# CCM_0011.net
KiCad netlist of a schematic drawn in EAGLE
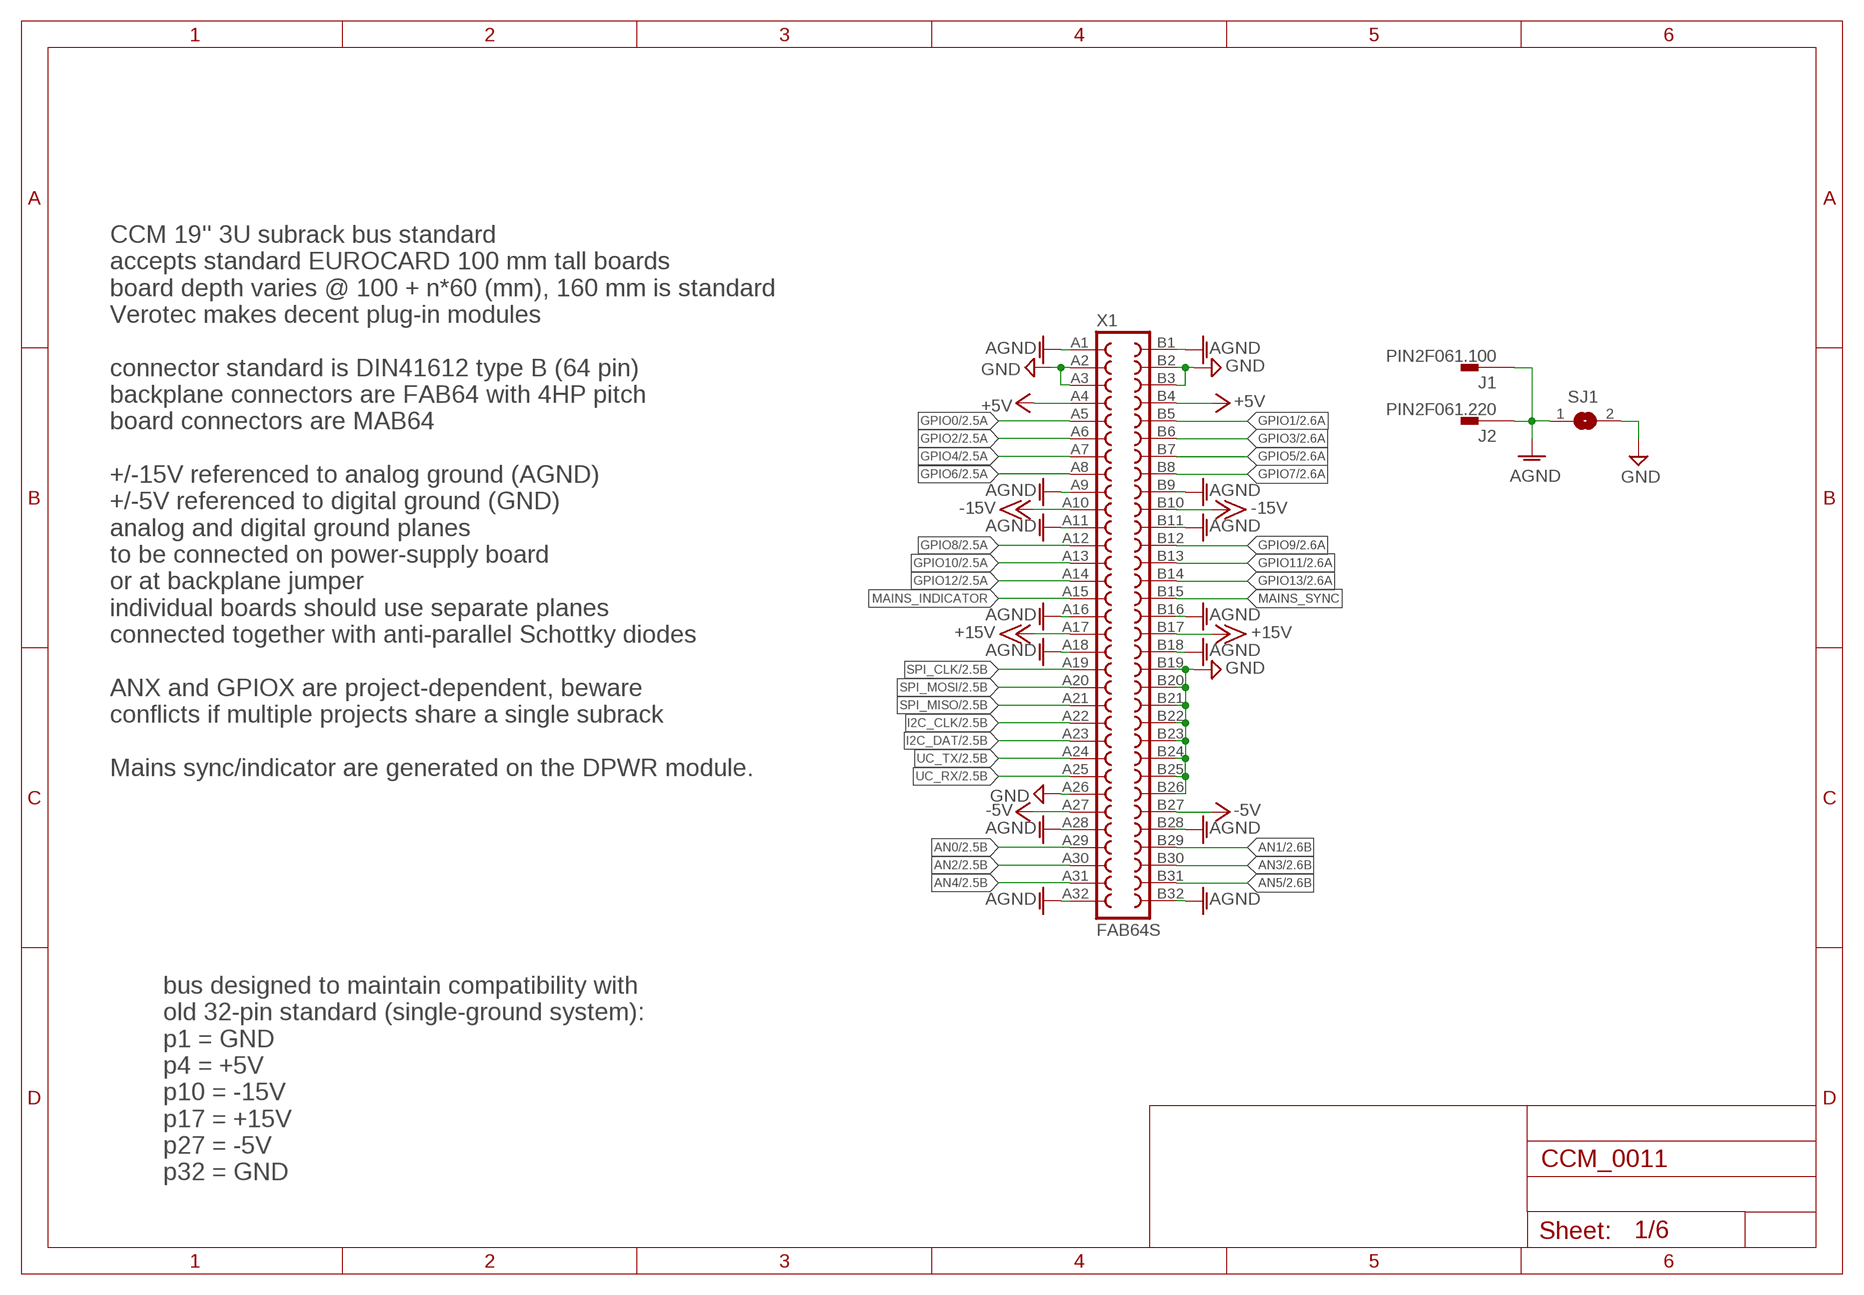
[diagram p0: schematic, sheet 1]
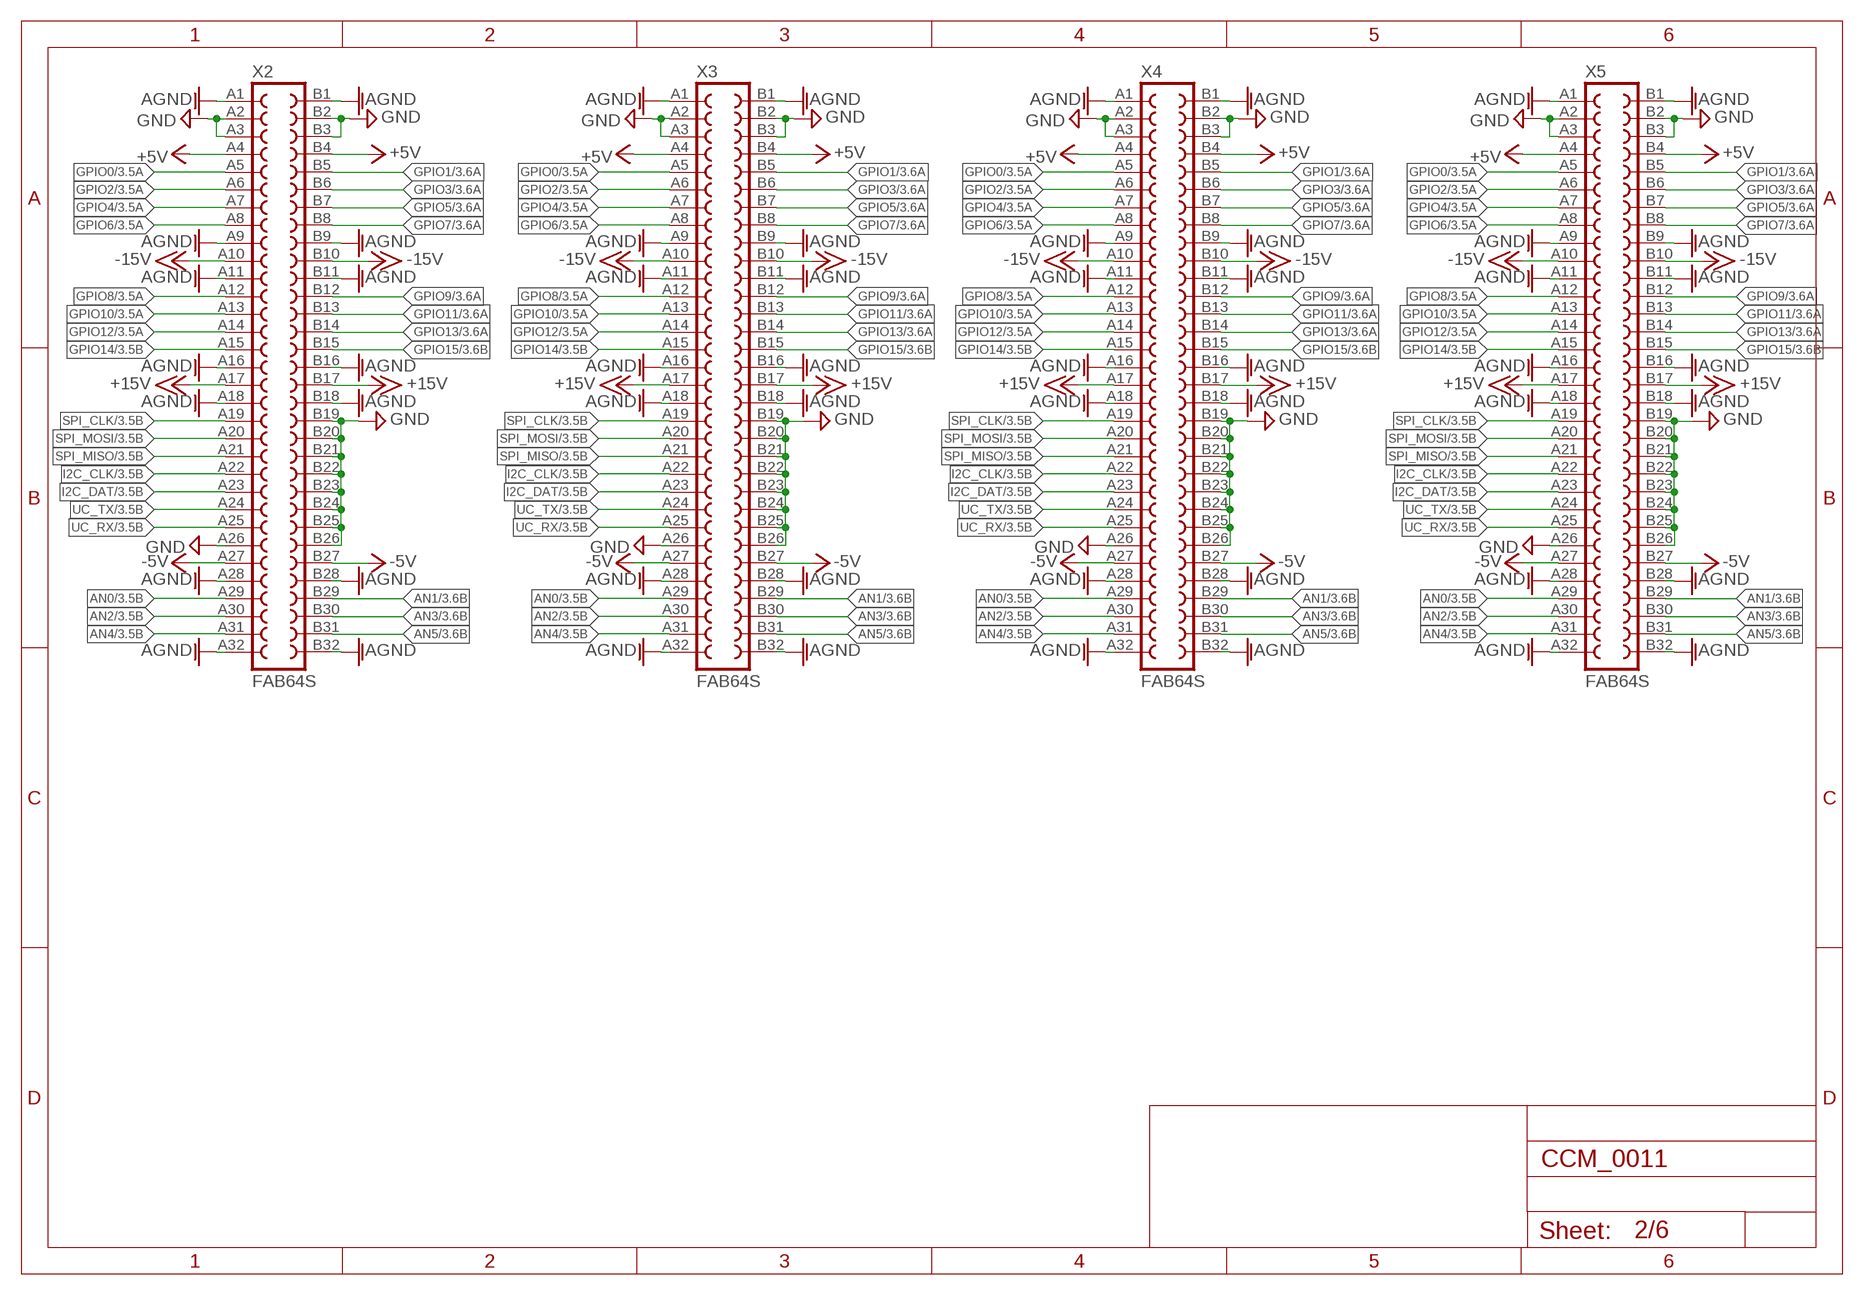
[diagram p1: schematic, sheet 2]
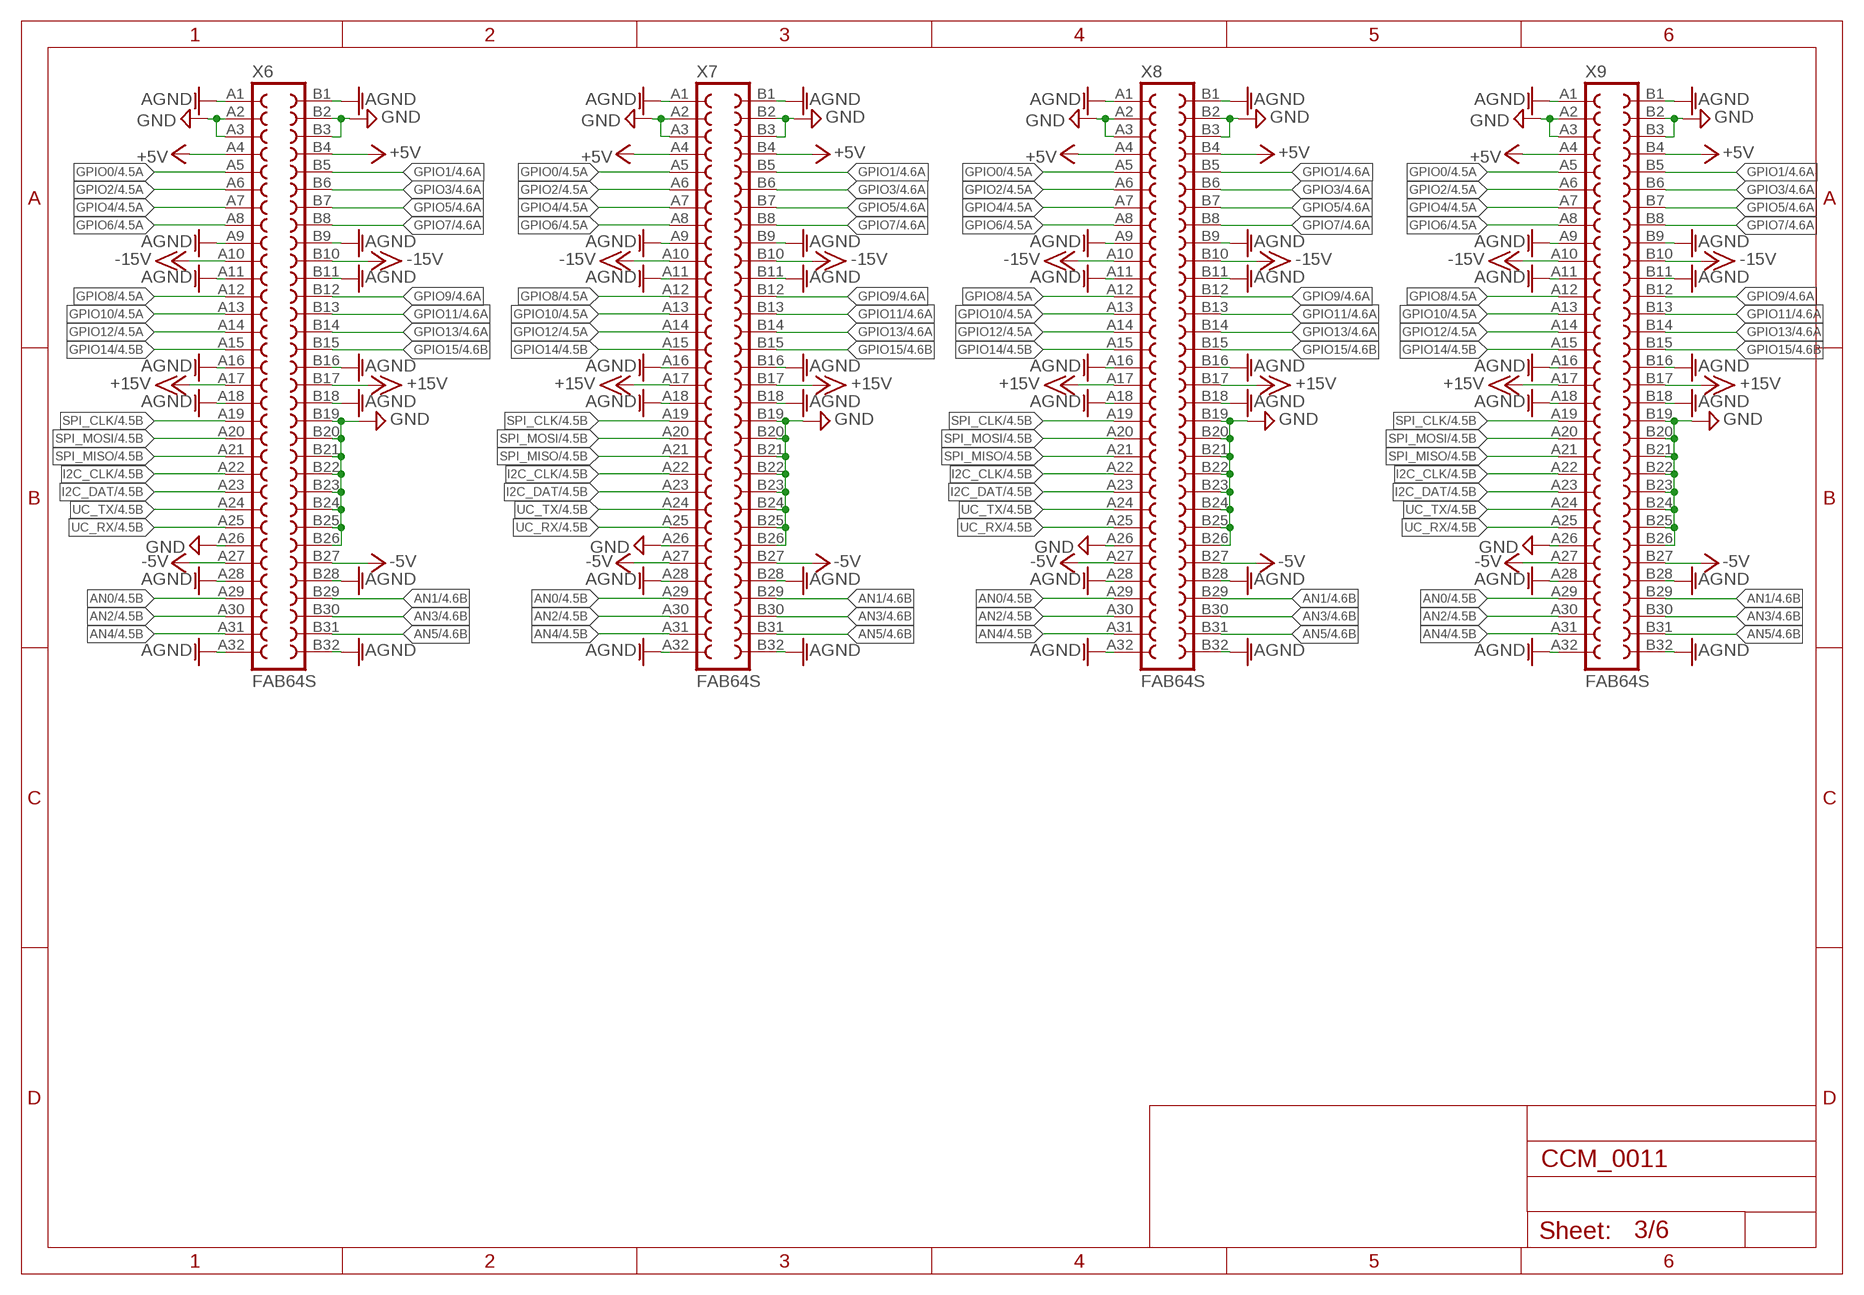
[diagram p2: schematic, sheet 3]
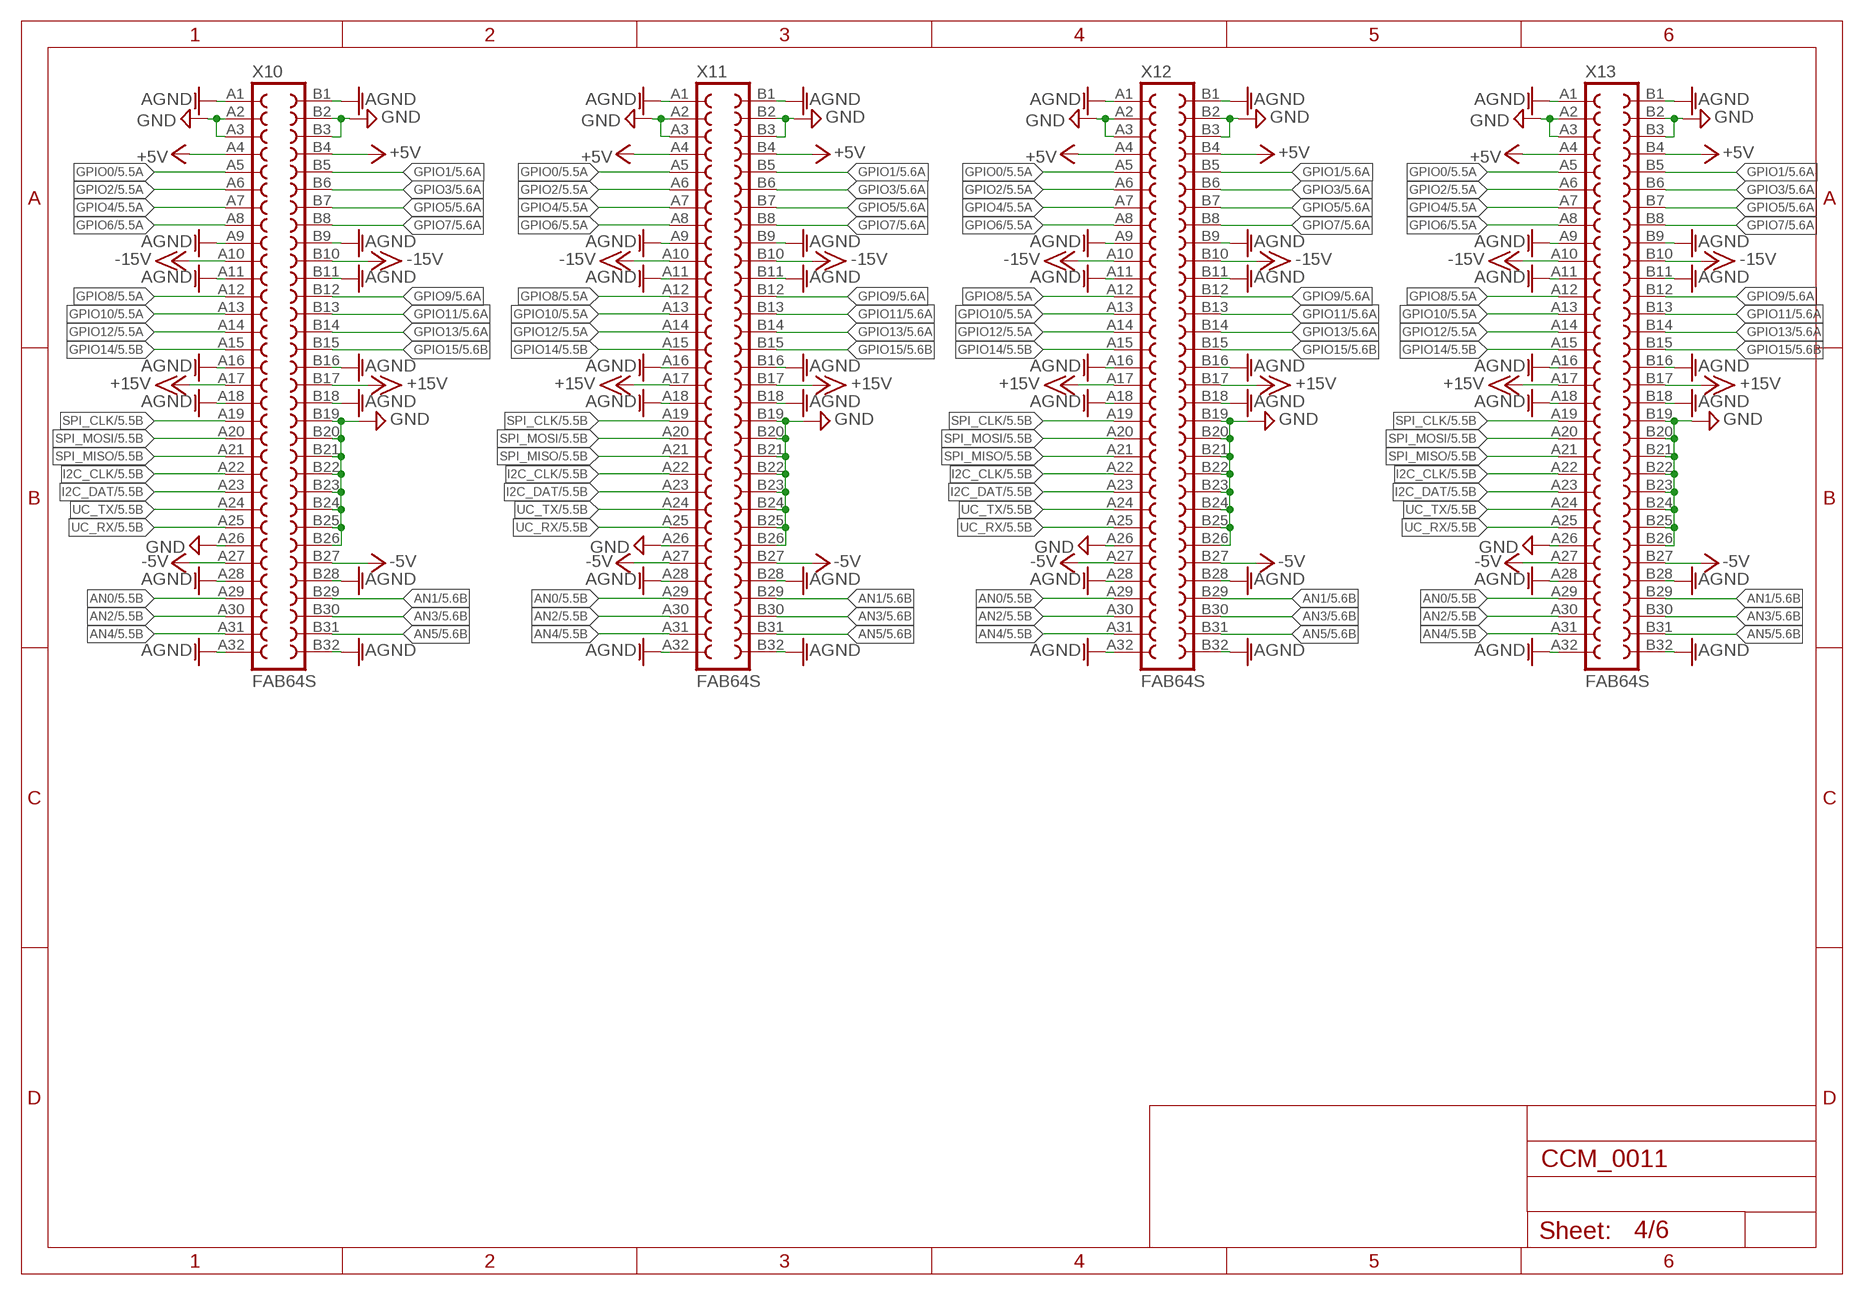
[diagram p3: schematic, sheet 4]
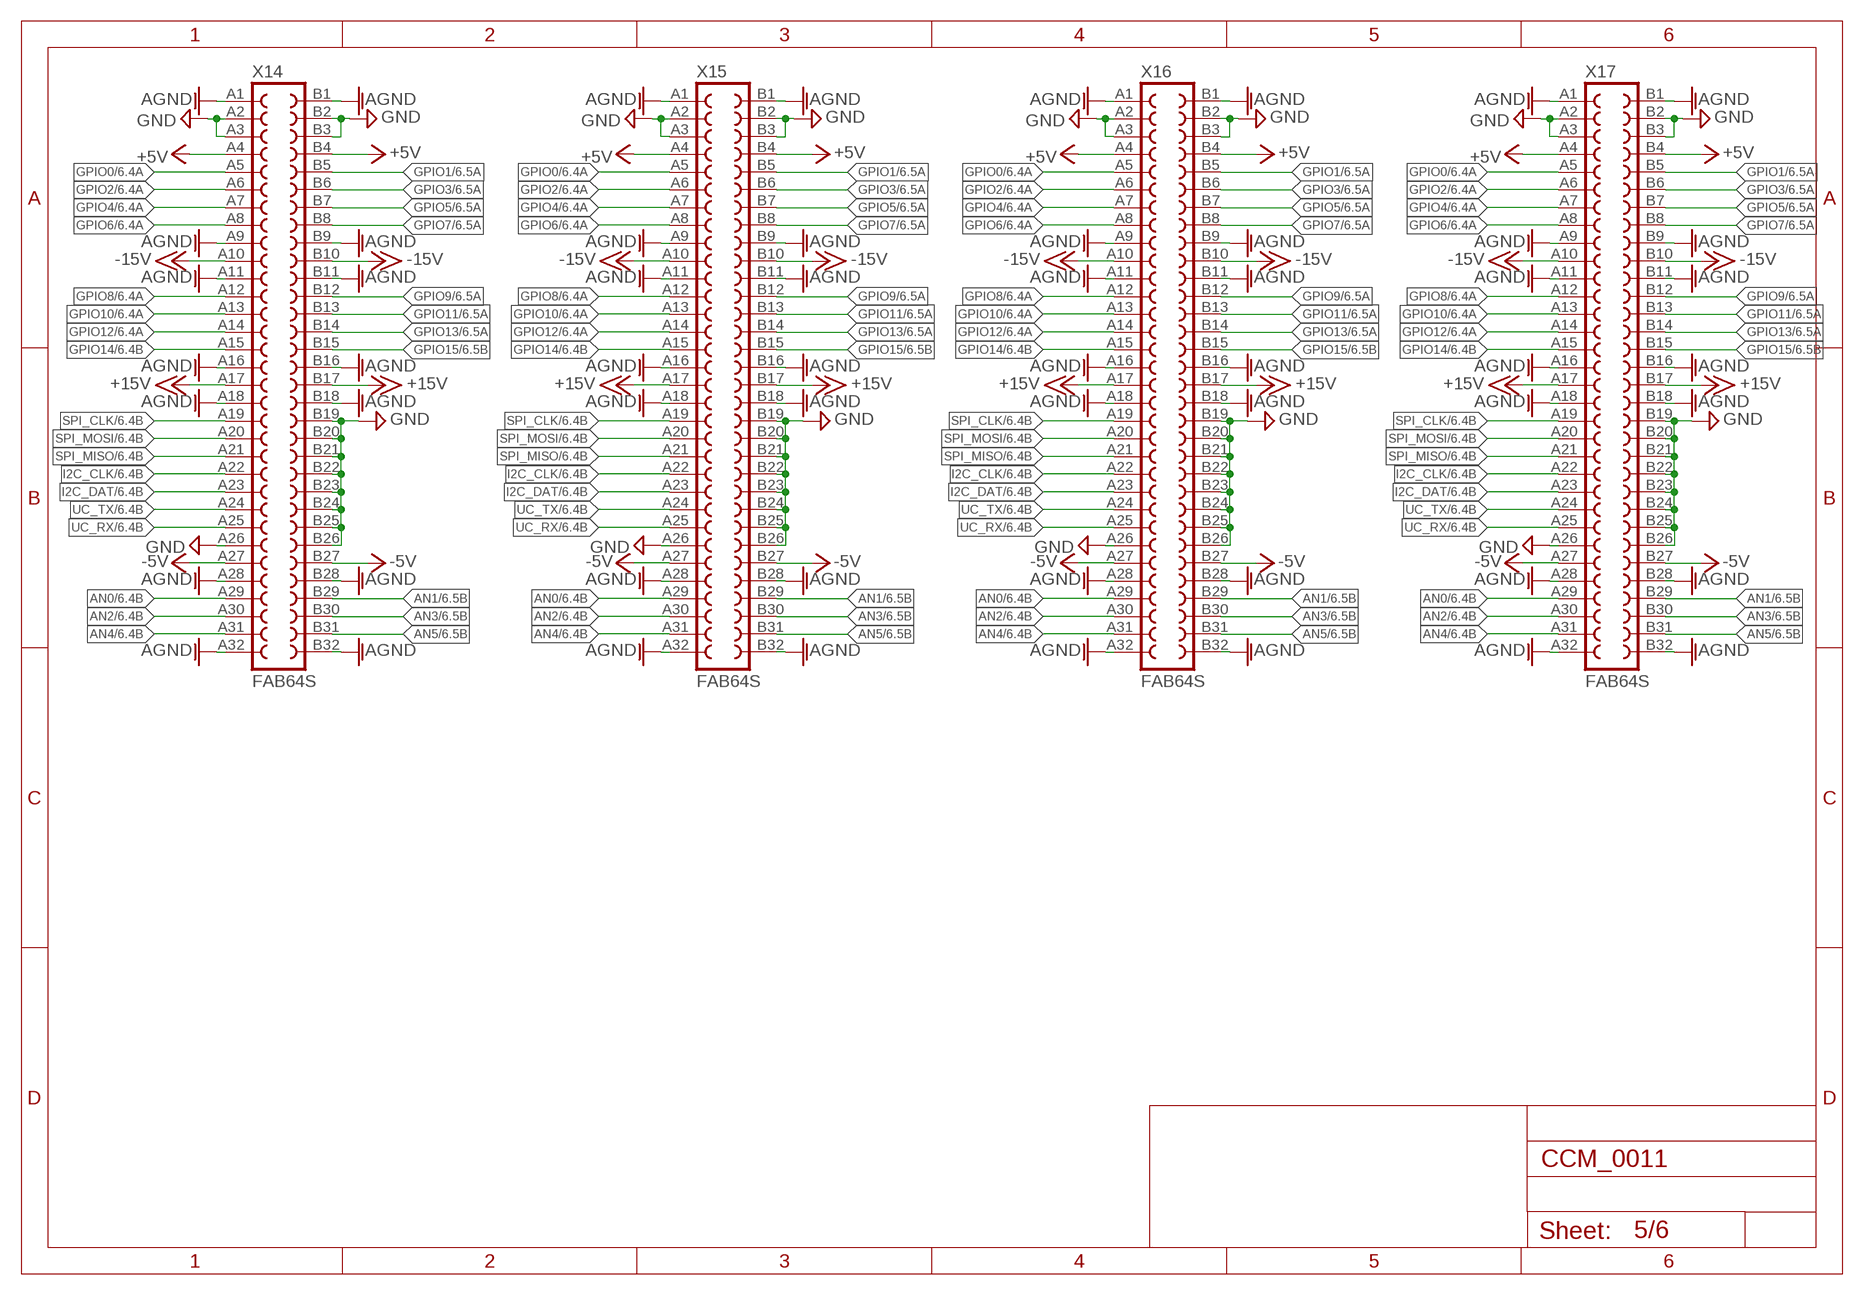
[diagram p4: schematic, sheet 5]
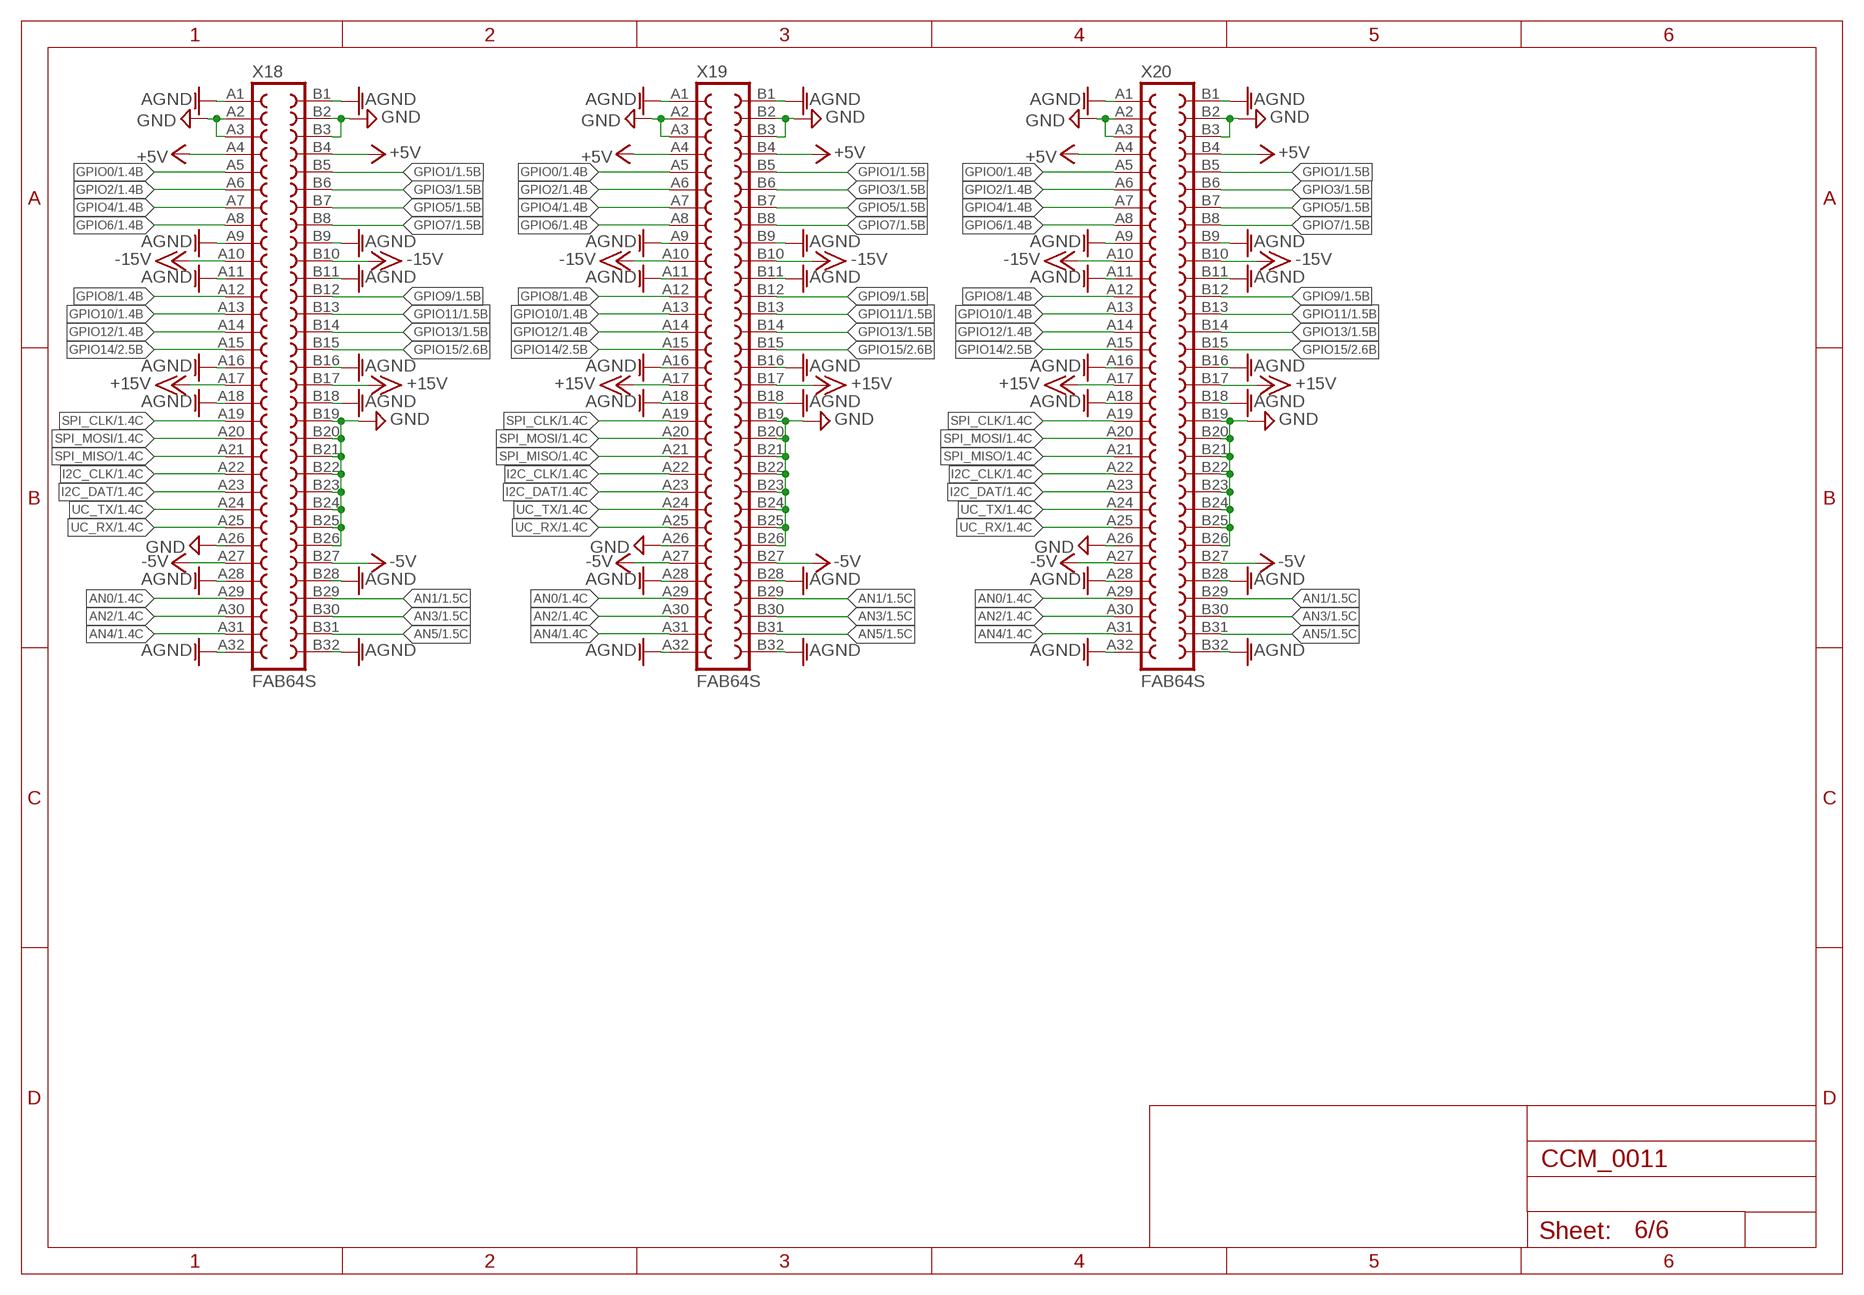
[diagram p5: schematic, sheet 6]

(export (version "E")
  (design (tool "Eeschema 10.0.6"))
  (components
    (comp (ref "X14")
      (value "FAB64S")
      (footprint "eagle-import:FAB64S")
      (libsource (lib "eagle-import") (part "FAB64S"))
    )
    (comp (ref "X15")
      (value "FAB64S")
      (footprint "eagle-import:FAB64S")
      (libsource (lib "eagle-import") (part "FAB64S"))
    )
    (comp (ref "X16")
      (value "FAB64S")
      (footprint "eagle-import:FAB64S")
      (libsource (lib "eagle-import") (part "FAB64S"))
    )
    (comp (ref "X17")
      (value "FAB64S")
      (footprint "eagle-import:FAB64S")
      (libsource (lib "eagle-import") (part "FAB64S"))
    )
    (comp (ref "X6")
      (value "FAB64S")
      (footprint "eagle-import:FAB64S")
      (libsource (lib "eagle-import") (part "FAB64S"))
    )
    (comp (ref "X7")
      (value "FAB64S")
      (footprint "eagle-import:FAB64S")
      (libsource (lib "eagle-import") (part "FAB64S"))
    )
    (comp (ref "X8")
      (value "FAB64S")
      (footprint "eagle-import:FAB64S")
      (libsource (lib "eagle-import") (part "FAB64S"))
    )
    (comp (ref "X9")
      (value "FAB64S")
      (footprint "eagle-import:FAB64S")
      (libsource (lib "eagle-import") (part "FAB64S"))
    )
    (comp (ref "X2")
      (value "FAB64S")
      (footprint "eagle-import:FAB64S")
      (libsource (lib "eagle-import") (part "FAB64S"))
    )
    (comp (ref "X3")
      (value "FAB64S")
      (footprint "eagle-import:FAB64S")
      (libsource (lib "eagle-import") (part "FAB64S"))
    )
    (comp (ref "X4")
      (value "FAB64S")
      (footprint "eagle-import:FAB64S")
      (libsource (lib "eagle-import") (part "FAB64S"))
    )
    (comp (ref "X5")
      (value "FAB64S")
      (footprint "eagle-import:FAB64S")
      (libsource (lib "eagle-import") (part "FAB64S"))
    )
    (comp (ref "X10")
      (value "FAB64S")
      (footprint "eagle-import:FAB64S")
      (libsource (lib "eagle-import") (part "FAB64S"))
    )
    (comp (ref "X11")
      (value "FAB64S")
      (footprint "eagle-import:FAB64S")
      (libsource (lib "eagle-import") (part "FAB64S"))
    )
    (comp (ref "X12")
      (value "FAB64S")
      (footprint "eagle-import:FAB64S")
      (libsource (lib "eagle-import") (part "FAB64S"))
    )
    (comp (ref "X13")
      (value "FAB64S")
      (footprint "eagle-import:FAB64S")
      (libsource (lib "eagle-import") (part "FAB64S"))
    )
    (comp (ref "X18")
      (value "FAB64S")
      (footprint "eagle-import:FAB64S")
      (libsource (lib "eagle-import") (part "FAB64S"))
    )
    (comp (ref "X19")
      (value "FAB64S")
      (footprint "eagle-import:FAB64S")
      (libsource (lib "eagle-import") (part "FAB64S"))
    )
    (comp (ref "X20")
      (value "FAB64S")
      (footprint "eagle-import:FAB64S")
      (libsource (lib "eagle-import") (part "FAB64S"))
    )
    (comp (ref "J1")
      (value "PIN2F061.100")
      (footprint "eagle-import:F061.100")
      (libsource (lib "eagle-import") (part "PIN2F061.100"))
    )
    (comp (ref "J2")
      (value "PIN2F061.220")
      (footprint "eagle-import:F061.220")
      (libsource (lib "eagle-import") (part "PIN2F061.220"))
    )
    (comp (ref "SJ1") (value "SJ") (footprint "eagle-import:SJ") (libsource (lib "eagle-import") (part "SJ")))
    (comp (ref "X1")
      (value "FAB64S")
      (footprint "eagle-import:FAB64S")
      (libsource (lib "eagle-import") (part "noah_FAB64S"))
    )
  )
  (nets
    (net (code "1") (name "+5V") (class "Default")
      (node (ref "X1") (pin "A4") (pinfunction "A4_A4") (pintype "passive"))
      (node (ref "X1") (pin "B4") (pinfunction "B4_B4") (pintype "passive"))
      (node (ref "X10") (pin "A4") (pinfunction "A4_A4") (pintype "passive"))
      (node (ref "X10") (pin "B4") (pinfunction "B4_B4") (pintype "passive"))
      (node (ref "X11") (pin "A4") (pinfunction "A4_A4") (pintype "passive"))
      (node (ref "X11") (pin "B4") (pinfunction "B4_B4") (pintype "passive"))
      (node (ref "X12") (pin "A4") (pinfunction "A4_A4") (pintype "passive"))
      (node (ref "X12") (pin "B4") (pinfunction "B4_B4") (pintype "passive"))
      (node (ref "X13") (pin "A4") (pinfunction "A4_A4") (pintype "passive"))
      (node (ref "X13") (pin "B4") (pinfunction "B4_B4") (pintype "passive"))
      (node (ref "X14") (pin "A4") (pinfunction "A4_A4") (pintype "passive"))
      (node (ref "X14") (pin "B4") (pinfunction "B4_B4") (pintype "passive"))
      (node (ref "X15") (pin "A4") (pinfunction "A4_A4") (pintype "passive"))
      (node (ref "X15") (pin "B4") (pinfunction "B4_B4") (pintype "passive"))
      (node (ref "X16") (pin "A4") (pinfunction "A4_A4") (pintype "passive"))
      (node (ref "X16") (pin "B4") (pinfunction "B4_B4") (pintype "passive"))
      (node (ref "X17") (pin "A4") (pinfunction "A4_A4") (pintype "passive"))
      (node (ref "X17") (pin "B4") (pinfunction "B4_B4") (pintype "passive"))
      (node (ref "X18") (pin "A4") (pinfunction "A4_A4") (pintype "passive"))
      (node (ref "X18") (pin "B4") (pinfunction "B4_B4") (pintype "passive"))
      (node (ref "X19") (pin "A4") (pinfunction "A4_A4") (pintype "passive"))
      (node (ref "X19") (pin "B4") (pinfunction "B4_B4") (pintype "passive"))
      (node (ref "X2") (pin "A4") (pinfunction "A4_A4") (pintype "passive"))
      (node (ref "X2") (pin "B4") (pinfunction "B4_B4") (pintype "passive"))
      (node (ref "X20") (pin "A4") (pinfunction "A4_A4") (pintype "passive"))
      (node (ref "X20") (pin "B4") (pinfunction "B4_B4") (pintype "passive"))
      (node (ref "X3") (pin "A4") (pinfunction "A4_A4") (pintype "passive"))
      (node (ref "X3") (pin "B4") (pinfunction "B4_B4") (pintype "passive"))
      (node (ref "X4") (pin "A4") (pinfunction "A4_A4") (pintype "passive"))
      (node (ref "X4") (pin "B4") (pinfunction "B4_B4") (pintype "passive"))
      (node (ref "X5") (pin "A4") (pinfunction "A4_A4") (pintype "passive"))
      (node (ref "X5") (pin "B4") (pinfunction "B4_B4") (pintype "passive"))
      (node (ref "X6") (pin "A4") (pinfunction "A4_A4") (pintype "passive"))
      (node (ref "X6") (pin "B4") (pinfunction "B4_B4") (pintype "passive"))
      (node (ref "X7") (pin "A4") (pinfunction "A4_A4") (pintype "passive"))
      (node (ref "X7") (pin "B4") (pinfunction "B4_B4") (pintype "passive"))
      (node (ref "X8") (pin "A4") (pinfunction "A4_A4") (pintype "passive"))
      (node (ref "X8") (pin "B4") (pinfunction "B4_B4") (pintype "passive"))
      (node (ref "X9") (pin "A4") (pinfunction "A4_A4") (pintype "passive"))
      (node (ref "X9") (pin "B4") (pinfunction "B4_B4") (pintype "passive"))
    )
    (net (code "2") (name "+15V") (class "Default")
      (node (ref "X1") (pin "A17") (pinfunction "A17_A17") (pintype "passive"))
      (node (ref "X1") (pin "B17") (pinfunction "B17_B17") (pintype "passive"))
      (node (ref "X10") (pin "A17") (pinfunction "A17_A17") (pintype "passive"))
      (node (ref "X10") (pin "B17") (pinfunction "B17_B17") (pintype "passive"))
      (node (ref "X11") (pin "A17") (pinfunction "A17_A17") (pintype "passive"))
      (node (ref "X11") (pin "B17") (pinfunction "B17_B17") (pintype "passive"))
      (node (ref "X12") (pin "A17") (pinfunction "A17_A17") (pintype "passive"))
      (node (ref "X12") (pin "B17") (pinfunction "B17_B17") (pintype "passive"))
      (node (ref "X13") (pin "A17") (pinfunction "A17_A17") (pintype "passive"))
      (node (ref "X13") (pin "B17") (pinfunction "B17_B17") (pintype "passive"))
      (node (ref "X14") (pin "A17") (pinfunction "A17_A17") (pintype "passive"))
      (node (ref "X14") (pin "B17") (pinfunction "B17_B17") (pintype "passive"))
      (node (ref "X15") (pin "A17") (pinfunction "A17_A17") (pintype "passive"))
      (node (ref "X15") (pin "B17") (pinfunction "B17_B17") (pintype "passive"))
      (node (ref "X16") (pin "A17") (pinfunction "A17_A17") (pintype "passive"))
      (node (ref "X16") (pin "B17") (pinfunction "B17_B17") (pintype "passive"))
      (node (ref "X17") (pin "A17") (pinfunction "A17_A17") (pintype "passive"))
      (node (ref "X17") (pin "B17") (pinfunction "B17_B17") (pintype "passive"))
      (node (ref "X18") (pin "A17") (pinfunction "A17_A17") (pintype "passive"))
      (node (ref "X18") (pin "B17") (pinfunction "B17_B17") (pintype "passive"))
      (node (ref "X19") (pin "A17") (pinfunction "A17_A17") (pintype "passive"))
      (node (ref "X19") (pin "B17") (pinfunction "B17_B17") (pintype "passive"))
      (node (ref "X2") (pin "A17") (pinfunction "A17_A17") (pintype "passive"))
      (node (ref "X2") (pin "B17") (pinfunction "B17_B17") (pintype "passive"))
      (node (ref "X20") (pin "A17") (pinfunction "A17_A17") (pintype "passive"))
      (node (ref "X20") (pin "B17") (pinfunction "B17_B17") (pintype "passive"))
      (node (ref "X3") (pin "A17") (pinfunction "A17_A17") (pintype "passive"))
      (node (ref "X3") (pin "B17") (pinfunction "B17_B17") (pintype "passive"))
      (node (ref "X4") (pin "A17") (pinfunction "A17_A17") (pintype "passive"))
      (node (ref "X4") (pin "B17") (pinfunction "B17_B17") (pintype "passive"))
      (node (ref "X5") (pin "A17") (pinfunction "A17_A17") (pintype "passive"))
      (node (ref "X5") (pin "B17") (pinfunction "B17_B17") (pintype "passive"))
      (node (ref "X6") (pin "A17") (pinfunction "A17_A17") (pintype "passive"))
      (node (ref "X6") (pin "B17") (pinfunction "B17_B17") (pintype "passive"))
      (node (ref "X7") (pin "A17") (pinfunction "A17_A17") (pintype "passive"))
      (node (ref "X7") (pin "B17") (pinfunction "B17_B17") (pintype "passive"))
      (node (ref "X8") (pin "A17") (pinfunction "A17_A17") (pintype "passive"))
      (node (ref "X8") (pin "B17") (pinfunction "B17_B17") (pintype "passive"))
      (node (ref "X9") (pin "A17") (pinfunction "A17_A17") (pintype "passive"))
      (node (ref "X9") (pin "B17") (pinfunction "B17_B17") (pintype "passive"))
    )
    (net (code "3") (name "-5V") (class "Default")
      (node (ref "X1") (pin "A27") (pinfunction "A27_A27") (pintype "passive"))
      (node (ref "X1") (pin "B27") (pinfunction "B27_B27") (pintype "passive"))
      (node (ref "X10") (pin "A27") (pinfunction "A27_A27") (pintype "passive"))
      (node (ref "X10") (pin "B27") (pinfunction "B27_B27") (pintype "passive"))
      (node (ref "X11") (pin "A27") (pinfunction "A27_A27") (pintype "passive"))
      (node (ref "X11") (pin "B27") (pinfunction "B27_B27") (pintype "passive"))
      (node (ref "X12") (pin "A27") (pinfunction "A27_A27") (pintype "passive"))
      (node (ref "X12") (pin "B27") (pinfunction "B27_B27") (pintype "passive"))
      (node (ref "X13") (pin "A27") (pinfunction "A27_A27") (pintype "passive"))
      (node (ref "X13") (pin "B27") (pinfunction "B27_B27") (pintype "passive"))
      (node (ref "X14") (pin "A27") (pinfunction "A27_A27") (pintype "passive"))
      (node (ref "X14") (pin "B27") (pinfunction "B27_B27") (pintype "passive"))
      (node (ref "X15") (pin "A27") (pinfunction "A27_A27") (pintype "passive"))
      (node (ref "X15") (pin "B27") (pinfunction "B27_B27") (pintype "passive"))
      (node (ref "X16") (pin "A27") (pinfunction "A27_A27") (pintype "passive"))
      (node (ref "X16") (pin "B27") (pinfunction "B27_B27") (pintype "passive"))
      (node (ref "X17") (pin "A27") (pinfunction "A27_A27") (pintype "passive"))
      (node (ref "X17") (pin "B27") (pinfunction "B27_B27") (pintype "passive"))
      (node (ref "X18") (pin "A27") (pinfunction "A27_A27") (pintype "passive"))
      (node (ref "X18") (pin "B27") (pinfunction "B27_B27") (pintype "passive"))
      (node (ref "X19") (pin "A27") (pinfunction "A27_A27") (pintype "passive"))
      (node (ref "X19") (pin "B27") (pinfunction "B27_B27") (pintype "passive"))
      (node (ref "X2") (pin "A27") (pinfunction "A27_A27") (pintype "passive"))
      (node (ref "X2") (pin "B27") (pinfunction "B27_B27") (pintype "passive"))
      (node (ref "X20") (pin "A27") (pinfunction "A27_A27") (pintype "passive"))
      (node (ref "X20") (pin "B27") (pinfunction "B27_B27") (pintype "passive"))
      (node (ref "X3") (pin "A27") (pinfunction "A27_A27") (pintype "passive"))
      (node (ref "X3") (pin "B27") (pinfunction "B27_B27") (pintype "passive"))
      (node (ref "X4") (pin "A27") (pinfunction "A27_A27") (pintype "passive"))
      (node (ref "X4") (pin "B27") (pinfunction "B27_B27") (pintype "passive"))
      (node (ref "X5") (pin "A27") (pinfunction "A27_A27") (pintype "passive"))
      (node (ref "X5") (pin "B27") (pinfunction "B27_B27") (pintype "passive"))
      (node (ref "X6") (pin "A27") (pinfunction "A27_A27") (pintype "passive"))
      (node (ref "X6") (pin "B27") (pinfunction "B27_B27") (pintype "passive"))
      (node (ref "X7") (pin "A27") (pinfunction "A27_A27") (pintype "passive"))
      (node (ref "X7") (pin "B27") (pinfunction "B27_B27") (pintype "passive"))
      (node (ref "X8") (pin "A27") (pinfunction "A27_A27") (pintype "passive"))
      (node (ref "X8") (pin "B27") (pinfunction "B27_B27") (pintype "passive"))
      (node (ref "X9") (pin "A27") (pinfunction "A27_A27") (pintype "passive"))
      (node (ref "X9") (pin "B27") (pinfunction "B27_B27") (pintype "passive"))
    )
    (net (code "4") (name "-15V") (class "Default")
      (node (ref "X1") (pin "A10") (pinfunction "A10_A10") (pintype "passive"))
      (node (ref "X1") (pin "B10") (pinfunction "B10_B10") (pintype "passive"))
      (node (ref "X10") (pin "A10") (pinfunction "A10_A10") (pintype "passive"))
      (node (ref "X10") (pin "B10") (pinfunction "B10_B10") (pintype "passive"))
      (node (ref "X11") (pin "A10") (pinfunction "A10_A10") (pintype "passive"))
      (node (ref "X11") (pin "B10") (pinfunction "B10_B10") (pintype "passive"))
      (node (ref "X12") (pin "A10") (pinfunction "A10_A10") (pintype "passive"))
      (node (ref "X12") (pin "B10") (pinfunction "B10_B10") (pintype "passive"))
      (node (ref "X13") (pin "A10") (pinfunction "A10_A10") (pintype "passive"))
      (node (ref "X13") (pin "B10") (pinfunction "B10_B10") (pintype "passive"))
      (node (ref "X14") (pin "A10") (pinfunction "A10_A10") (pintype "passive"))
      (node (ref "X14") (pin "B10") (pinfunction "B10_B10") (pintype "passive"))
      (node (ref "X15") (pin "A10") (pinfunction "A10_A10") (pintype "passive"))
      (node (ref "X15") (pin "B10") (pinfunction "B10_B10") (pintype "passive"))
      (node (ref "X16") (pin "A10") (pinfunction "A10_A10") (pintype "passive"))
      (node (ref "X16") (pin "B10") (pinfunction "B10_B10") (pintype "passive"))
      (node (ref "X17") (pin "A10") (pinfunction "A10_A10") (pintype "passive"))
      (node (ref "X17") (pin "B10") (pinfunction "B10_B10") (pintype "passive"))
      (node (ref "X18") (pin "A10") (pinfunction "A10_A10") (pintype "passive"))
      (node (ref "X18") (pin "B10") (pinfunction "B10_B10") (pintype "passive"))
      (node (ref "X19") (pin "A10") (pinfunction "A10_A10") (pintype "passive"))
      (node (ref "X19") (pin "B10") (pinfunction "B10_B10") (pintype "passive"))
      (node (ref "X2") (pin "A10") (pinfunction "A10_A10") (pintype "passive"))
      (node (ref "X2") (pin "B10") (pinfunction "B10_B10") (pintype "passive"))
      (node (ref "X20") (pin "A10") (pinfunction "A10_A10") (pintype "passive"))
      (node (ref "X20") (pin "B10") (pinfunction "B10_B10") (pintype "passive"))
      (node (ref "X3") (pin "A10") (pinfunction "A10_A10") (pintype "passive"))
      (node (ref "X3") (pin "B10") (pinfunction "B10_B10") (pintype "passive"))
      (node (ref "X4") (pin "A10") (pinfunction "A10_A10") (pintype "passive"))
      (node (ref "X4") (pin "B10") (pinfunction "B10_B10") (pintype "passive"))
      (node (ref "X5") (pin "A10") (pinfunction "A10_A10") (pintype "passive"))
      (node (ref "X5") (pin "B10") (pinfunction "B10_B10") (pintype "passive"))
      (node (ref "X6") (pin "A10") (pinfunction "A10_A10") (pintype "passive"))
      (node (ref "X6") (pin "B10") (pinfunction "B10_B10") (pintype "passive"))
      (node (ref "X7") (pin "A10") (pinfunction "A10_A10") (pintype "passive"))
      (node (ref "X7") (pin "B10") (pinfunction "B10_B10") (pintype "passive"))
      (node (ref "X8") (pin "A10") (pinfunction "A10_A10") (pintype "passive"))
      (node (ref "X8") (pin "B10") (pinfunction "B10_B10") (pintype "passive"))
      (node (ref "X9") (pin "A10") (pinfunction "A10_A10") (pintype "passive"))
      (node (ref "X9") (pin "B10") (pinfunction "B10_B10") (pintype "passive"))
    )
    (net (code "5") (name "AGND") (class "Default")
      (node (ref "J1") (pin "A1") (pinfunction "1_A1") (pintype "passive"))
      (node (ref "J1") (pin "A2") (pinfunction "1_A2") (pintype "passive"))
      (node (ref "J2") (pin "1A") (pinfunction "1_1A") (pintype "passive"))
      (node (ref "J2") (pin "1B") (pinfunction "1_1B") (pintype "passive"))
      (node (ref "SJ1") (pin "1") (pinfunction "1_1") (pintype "passive"))
      (node (ref "X1") (pin "A1") (pinfunction "A1_A1") (pintype "passive"))
      (node (ref "X1") (pin "A11") (pinfunction "A11_A11") (pintype "passive"))
      (node (ref "X1") (pin "A16") (pinfunction "A16_A16") (pintype "passive"))
      (node (ref "X1") (pin "A18") (pinfunction "A18_A18") (pintype "passive"))
      (node (ref "X1") (pin "A28") (pinfunction "A28_A28") (pintype "passive"))
      (node (ref "X1") (pin "A32") (pinfunction "A32_A32") (pintype "passive"))
      (node (ref "X1") (pin "A9") (pinfunction "A9_A9") (pintype "passive"))
      (node (ref "X1") (pin "B1") (pinfunction "B1_B1") (pintype "passive"))
      (node (ref "X1") (pin "B11") (pinfunction "B11_B11") (pintype "passive"))
      (node (ref "X1") (pin "B16") (pinfunction "B16_B16") (pintype "passive"))
      (node (ref "X1") (pin "B18") (pinfunction "B18_B18") (pintype "passive"))
      (node (ref "X1") (pin "B28") (pinfunction "B28_B28") (pintype "passive"))
      (node (ref "X1") (pin "B32") (pinfunction "B32_B32") (pintype "passive"))
      (node (ref "X1") (pin "B9") (pinfunction "B9_B9") (pintype "passive"))
      (node (ref "X10") (pin "A1") (pinfunction "A1_A1") (pintype "passive"))
      (node (ref "X10") (pin "A11") (pinfunction "A11_A11") (pintype "passive"))
      (node (ref "X10") (pin "A16") (pinfunction "A16_A16") (pintype "passive"))
      (node (ref "X10") (pin "A18") (pinfunction "A18_A18") (pintype "passive"))
      (node (ref "X10") (pin "A28") (pinfunction "A28_A28") (pintype "passive"))
      (node (ref "X10") (pin "A32") (pinfunction "A32_A32") (pintype "passive"))
      (node (ref "X10") (pin "A9") (pinfunction "A9_A9") (pintype "passive"))
      (node (ref "X10") (pin "B1") (pinfunction "B1_B1") (pintype "passive"))
      (node (ref "X10") (pin "B11") (pinfunction "B11_B11") (pintype "passive"))
      (node (ref "X10") (pin "B16") (pinfunction "B16_B16") (pintype "passive"))
      (node (ref "X10") (pin "B18") (pinfunction "B18_B18") (pintype "passive"))
      (node (ref "X10") (pin "B28") (pinfunction "B28_B28") (pintype "passive"))
      (node (ref "X10") (pin "B32") (pinfunction "B32_B32") (pintype "passive"))
      (node (ref "X10") (pin "B9") (pinfunction "B9_B9") (pintype "passive"))
      (node (ref "X11") (pin "A1") (pinfunction "A1_A1") (pintype "passive"))
      (node (ref "X11") (pin "A11") (pinfunction "A11_A11") (pintype "passive"))
      (node (ref "X11") (pin "A16") (pinfunction "A16_A16") (pintype "passive"))
      (node (ref "X11") (pin "A18") (pinfunction "A18_A18") (pintype "passive"))
      (node (ref "X11") (pin "A28") (pinfunction "A28_A28") (pintype "passive"))
      (node (ref "X11") (pin "A32") (pinfunction "A32_A32") (pintype "passive"))
      (node (ref "X11") (pin "A9") (pinfunction "A9_A9") (pintype "passive"))
      (node (ref "X11") (pin "B1") (pinfunction "B1_B1") (pintype "passive"))
      (node (ref "X11") (pin "B11") (pinfunction "B11_B11") (pintype "passive"))
      (node (ref "X11") (pin "B16") (pinfunction "B16_B16") (pintype "passive"))
      (node (ref "X11") (pin "B18") (pinfunction "B18_B18") (pintype "passive"))
      (node (ref "X11") (pin "B28") (pinfunction "B28_B28") (pintype "passive"))
      (node (ref "X11") (pin "B32") (pinfunction "B32_B32") (pintype "passive"))
      (node (ref "X11") (pin "B9") (pinfunction "B9_B9") (pintype "passive"))
      (node (ref "X12") (pin "A1") (pinfunction "A1_A1") (pintype "passive"))
      (node (ref "X12") (pin "A11") (pinfunction "A11_A11") (pintype "passive"))
      (node (ref "X12") (pin "A16") (pinfunction "A16_A16") (pintype "passive"))
      (node (ref "X12") (pin "A18") (pinfunction "A18_A18") (pintype "passive"))
      (node (ref "X12") (pin "A28") (pinfunction "A28_A28") (pintype "passive"))
      (node (ref "X12") (pin "A32") (pinfunction "A32_A32") (pintype "passive"))
      (node (ref "X12") (pin "A9") (pinfunction "A9_A9") (pintype "passive"))
      (node (ref "X12") (pin "B1") (pinfunction "B1_B1") (pintype "passive"))
      (node (ref "X12") (pin "B11") (pinfunction "B11_B11") (pintype "passive"))
      (node (ref "X12") (pin "B16") (pinfunction "B16_B16") (pintype "passive"))
      (node (ref "X12") (pin "B18") (pinfunction "B18_B18") (pintype "passive"))
      (node (ref "X12") (pin "B28") (pinfunction "B28_B28") (pintype "passive"))
      (node (ref "X12") (pin "B32") (pinfunction "B32_B32") (pintype "passive"))
      (node (ref "X12") (pin "B9") (pinfunction "B9_B9") (pintype "passive"))
      (node (ref "X13") (pin "A1") (pinfunction "A1_A1") (pintype "passive"))
      (node (ref "X13") (pin "A11") (pinfunction "A11_A11") (pintype "passive"))
      (node (ref "X13") (pin "A16") (pinfunction "A16_A16") (pintype "passive"))
      (node (ref "X13") (pin "A18") (pinfunction "A18_A18") (pintype "passive"))
      (node (ref "X13") (pin "A28") (pinfunction "A28_A28") (pintype "passive"))
      (node (ref "X13") (pin "A32") (pinfunction "A32_A32") (pintype "passive"))
      (node (ref "X13") (pin "A9") (pinfunction "A9_A9") (pintype "passive"))
      (node (ref "X13") (pin "B1") (pinfunction "B1_B1") (pintype "passive"))
      (node (ref "X13") (pin "B11") (pinfunction "B11_B11") (pintype "passive"))
      (node (ref "X13") (pin "B16") (pinfunction "B16_B16") (pintype "passive"))
      (node (ref "X13") (pin "B18") (pinfunction "B18_B18") (pintype "passive"))
      (node (ref "X13") (pin "B28") (pinfunction "B28_B28") (pintype "passive"))
      (node (ref "X13") (pin "B32") (pinfunction "B32_B32") (pintype "passive"))
      (node (ref "X13") (pin "B9") (pinfunction "B9_B9") (pintype "passive"))
      (node (ref "X14") (pin "A1") (pinfunction "A1_A1") (pintype "passive"))
      (node (ref "X14") (pin "A11") (pinfunction "A11_A11") (pintype "passive"))
      (node (ref "X14") (pin "A16") (pinfunction "A16_A16") (pintype "passive"))
      (node (ref "X14") (pin "A18") (pinfunction "A18_A18") (pintype "passive"))
      (node (ref "X14") (pin "A28") (pinfunction "A28_A28") (pintype "passive"))
      (node (ref "X14") (pin "A32") (pinfunction "A32_A32") (pintype "passive"))
      (node (ref "X14") (pin "A9") (pinfunction "A9_A9") (pintype "passive"))
      (node (ref "X14") (pin "B1") (pinfunction "B1_B1") (pintype "passive"))
      (node (ref "X14") (pin "B11") (pinfunction "B11_B11") (pintype "passive"))
      (node (ref "X14") (pin "B16") (pinfunction "B16_B16") (pintype "passive"))
      (node (ref "X14") (pin "B18") (pinfunction "B18_B18") (pintype "passive"))
      (node (ref "X14") (pin "B28") (pinfunction "B28_B28") (pintype "passive"))
      (node (ref "X14") (pin "B32") (pinfunction "B32_B32") (pintype "passive"))
      (node (ref "X14") (pin "B9") (pinfunction "B9_B9") (pintype "passive"))
      (node (ref "X15") (pin "A1") (pinfunction "A1_A1") (pintype "passive"))
      (node (ref "X15") (pin "A11") (pinfunction "A11_A11") (pintype "passive"))
      (node (ref "X15") (pin "A16") (pinfunction "A16_A16") (pintype "passive"))
      (node (ref "X15") (pin "A18") (pinfunction "A18_A18") (pintype "passive"))
      (node (ref "X15") (pin "A28") (pinfunction "A28_A28") (pintype "passive"))
      (node (ref "X15") (pin "A32") (pinfunction "A32_A32") (pintype "passive"))
      (node (ref "X15") (pin "A9") (pinfunction "A9_A9") (pintype "passive"))
      (node (ref "X15") (pin "B1") (pinfunction "B1_B1") (pintype "passive"))
      (node (ref "X15") (pin "B11") (pinfunction "B11_B11") (pintype "passive"))
      (node (ref "X15") (pin "B16") (pinfunction "B16_B16") (pintype "passive"))
      (node (ref "X15") (pin "B18") (pinfunction "B18_B18") (pintype "passive"))
      (node (ref "X15") (pin "B28") (pinfunction "B28_B28") (pintype "passive"))
      (node (ref "X15") (pin "B32") (pinfunction "B32_B32") (pintype "passive"))
      (node (ref "X15") (pin "B9") (pinfunction "B9_B9") (pintype "passive"))
      (node (ref "X16") (pin "A1") (pinfunction "A1_A1") (pintype "passive"))
      (node (ref "X16") (pin "A11") (pinfunction "A11_A11") (pintype "passive"))
      (node (ref "X16") (pin "A16") (pinfunction "A16_A16") (pintype "passive"))
      (node (ref "X16") (pin "A18") (pinfunction "A18_A18") (pintype "passive"))
      (node (ref "X16") (pin "A28") (pinfunction "A28_A28") (pintype "passive"))
      (node (ref "X16") (pin "A32") (pinfunction "A32_A32") (pintype "passive"))
      (node (ref "X16") (pin "A9") (pinfunction "A9_A9") (pintype "passive"))
      (node (ref "X16") (pin "B1") (pinfunction "B1_B1") (pintype "passive"))
      (node (ref "X16") (pin "B11") (pinfunction "B11_B11") (pintype "passive"))
      (node (ref "X16") (pin "B16") (pinfunction "B16_B16") (pintype "passive"))
      (node (ref "X16") (pin "B18") (pinfunction "B18_B18") (pintype "passive"))
      (node (ref "X16") (pin "B28") (pinfunction "B28_B28") (pintype "passive"))
      (node (ref "X16") (pin "B32") (pinfunction "B32_B32") (pintype "passive"))
      (node (ref "X16") (pin "B9") (pinfunction "B9_B9") (pintype "passive"))
      (node (ref "X17") (pin "A1") (pinfunction "A1_A1") (pintype "passive"))
      (node (ref "X17") (pin "A11") (pinfunction "A11_A11") (pintype "passive"))
      (node (ref "X17") (pin "A16") (pinfunction "A16_A16") (pintype "passive"))
      (node (ref "X17") (pin "A18") (pinfunction "A18_A18") (pintype "passive"))
      (node (ref "X17") (pin "A28") (pinfunction "A28_A28") (pintype "passive"))
      (node (ref "X17") (pin "A32") (pinfunction "A32_A32") (pintype "passive"))
      (node (ref "X17") (pin "A9") (pinfunction "A9_A9") (pintype "passive"))
      (node (ref "X17") (pin "B1") (pinfunction "B1_B1") (pintype "passive"))
      (node (ref "X17") (pin "B11") (pinfunction "B11_B11") (pintype "passive"))
      (node (ref "X17") (pin "B16") (pinfunction "B16_B16") (pintype "passive"))
      (node (ref "X17") (pin "B18") (pinfunction "B18_B18") (pintype "passive"))
      (node (ref "X17") (pin "B28") (pinfunction "B28_B28") (pintype "passive"))
      (node (ref "X17") (pin "B32") (pinfunction "B32_B32") (pintype "passive"))
      (node (ref "X17") (pin "B9") (pinfunction "B9_B9") (pintype "passive"))
      (node (ref "X18") (pin "A1") (pinfunction "A1_A1") (pintype "passive"))
      (node (ref "X18") (pin "A11") (pinfunction "A11_A11") (pintype "passive"))
      (node (ref "X18") (pin "A16") (pinfunction "A16_A16") (pintype "passive"))
      (node (ref "X18") (pin "A18") (pinfunction "A18_A18") (pintype "passive"))
      (node (ref "X18") (pin "A28") (pinfunction "A28_A28") (pintype "passive"))
      (node (ref "X18") (pin "A32") (pinfunction "A32_A32") (pintype "passive"))
      (node (ref "X18") (pin "A9") (pinfunction "A9_A9") (pintype "passive"))
      (node (ref "X18") (pin "B1") (pinfunction "B1_B1") (pintype "passive"))
      (node (ref "X18") (pin "B11") (pinfunction "B11_B11") (pintype "passive"))
      (node (ref "X18") (pin "B16") (pinfunction "B16_B16") (pintype "passive"))
      (node (ref "X18") (pin "B18") (pinfunction "B18_B18") (pintype "passive"))
      (node (ref "X18") (pin "B28") (pinfunction "B28_B28") (pintype "passive"))
      (node (ref "X18") (pin "B32") (pinfunction "B32_B32") (pintype "passive"))
      (node (ref "X18") (pin "B9") (pinfunction "B9_B9") (pintype "passive"))
      (node (ref "X19") (pin "A1") (pinfunction "A1_A1") (pintype "passive"))
      (node (ref "X19") (pin "A11") (pinfunction "A11_A11") (pintype "passive"))
      (node (ref "X19") (pin "A16") (pinfunction "A16_A16") (pintype "passive"))
      (node (ref "X19") (pin "A18") (pinfunction "A18_A18") (pintype "passive"))
      (node (ref "X19") (pin "A28") (pinfunction "A28_A28") (pintype "passive"))
      (node (ref "X19") (pin "A32") (pinfunction "A32_A32") (pintype "passive"))
      (node (ref "X19") (pin "A9") (pinfunction "A9_A9") (pintype "passive"))
      (node (ref "X19") (pin "B1") (pinfunction "B1_B1") (pintype "passive"))
      (node (ref "X19") (pin "B11") (pinfunction "B11_B11") (pintype "passive"))
      (node (ref "X19") (pin "B16") (pinfunction "B16_B16") (pintype "passive"))
      (node (ref "X19") (pin "B18") (pinfunction "B18_B18") (pintype "passive"))
      (node (ref "X19") (pin "B28") (pinfunction "B28_B28") (pintype "passive"))
      (node (ref "X19") (pin "B32") (pinfunction "B32_B32") (pintype "passive"))
      (node (ref "X19") (pin "B9") (pinfunction "B9_B9") (pintype "passive"))
      (node (ref "X2") (pin "A1") (pinfunction "A1_A1") (pintype "passive"))
      (node (ref "X2") (pin "A11") (pinfunction "A11_A11") (pintype "passive"))
      (node (ref "X2") (pin "A16") (pinfunction "A16_A16") (pintype "passive"))
      (node (ref "X2") (pin "A18") (pinfunction "A18_A18") (pintype "passive"))
      (node (ref "X2") (pin "A28") (pinfunction "A28_A28") (pintype "passive"))
      (node (ref "X2") (pin "A32") (pinfunction "A32_A32") (pintype "passive"))
      (node (ref "X2") (pin "A9") (pinfunction "A9_A9") (pintype "passive"))
      (node (ref "X2") (pin "B1") (pinfunction "B1_B1") (pintype "passive"))
      (node (ref "X2") (pin "B11") (pinfunction "B11_B11") (pintype "passive"))
      (node (ref "X2") (pin "B16") (pinfunction "B16_B16") (pintype "passive"))
      (node (ref "X2") (pin "B18") (pinfunction "B18_B18") (pintype "passive"))
      (node (ref "X2") (pin "B28") (pinfunction "B28_B28") (pintype "passive"))
      (node (ref "X2") (pin "B32") (pinfunction "B32_B32") (pintype "passive"))
      (node (ref "X2") (pin "B9") (pinfunction "B9_B9") (pintype "passive"))
      (node (ref "X20") (pin "A1") (pinfunction "A1_A1") (pintype "passive"))
      (node (ref "X20") (pin "A11") (pinfunction "A11_A11") (pintype "passive"))
      (node (ref "X20") (pin "A16") (pinfunction "A16_A16") (pintype "passive"))
      (node (ref "X20") (pin "A18") (pinfunction "A18_A18") (pintype "passive"))
      (node (ref "X20") (pin "A28") (pinfunction "A28_A28") (pintype "passive"))
      (node (ref "X20") (pin "A32") (pinfunction "A32_A32") (pintype "passive"))
      (node (ref "X20") (pin "A9") (pinfunction "A9_A9") (pintype "passive"))
      (node (ref "X20") (pin "B1") (pinfunction "B1_B1") (pintype "passive"))
      (node (ref "X20") (pin "B11") (pinfunction "B11_B11") (pintype "passive"))
      (node (ref "X20") (pin "B16") (pinfunction "B16_B16") (pintype "passive"))
      (node (ref "X20") (pin "B18") (pinfunction "B18_B18") (pintype "passive"))
      (node (ref "X20") (pin "B28") (pinfunction "B28_B28") (pintype "passive"))
      (node (ref "X20") (pin "B32") (pinfunction "B32_B32") (pintype "passive"))
      (node (ref "X20") (pin "B9") (pinfunction "B9_B9") (pintype "passive"))
      (node (ref "X3") (pin "A1") (pinfunction "A1_A1") (pintype "passive"))
      (node (ref "X3") (pin "A11") (pinfunction "A11_A11") (pintype "passive"))
      (node (ref "X3") (pin "A16") (pinfunction "A16_A16") (pintype "passive"))
      (node (ref "X3") (pin "A18") (pinfunction "A18_A18") (pintype "passive"))
      (node (ref "X3") (pin "A28") (pinfunction "A28_A28") (pintype "passive"))
      (node (ref "X3") (pin "A32") (pinfunction "A32_A32") (pintype "passive"))
      (node (ref "X3") (pin "A9") (pinfunction "A9_A9") (pintype "passive"))
      (node (ref "X3") (pin "B1") (pinfunction "B1_B1") (pintype "passive"))
      (node (ref "X3") (pin "B11") (pinfunction "B11_B11") (pintype "passive"))
      (node (ref "X3") (pin "B16") (pinfunction "B16_B16") (pintype "passive"))
      (node (ref "X3") (pin "B18") (pinfunction "B18_B18") (pintype "passive"))
      (node (ref "X3") (pin "B28") (pinfunction "B28_B28") (pintype "passive"))
      (node (ref "X3") (pin "B32") (pinfunction "B32_B32") (pintype "passive"))
      (node (ref "X3") (pin "B9") (pinfunction "B9_B9") (pintype "passive"))
      (node (ref "X4") (pin "A1") (pinfunction "A1_A1") (pintype "passive"))
      (node (ref "X4") (pin "A11") (pinfunction "A11_A11") (pintype "passive"))
      (node (ref "X4") (pin "A16") (pinfunction "A16_A16") (pintype "passive"))
      (node (ref "X4") (pin "A18") (pinfunction "A18_A18") (pintype "passive"))
      (node (ref "X4") (pin "A28") (pinfunction "A28_A28") (pintype "passive"))
      (node (ref "X4") (pin "A32") (pinfunction "A32_A32") (pintype "passive"))
      (node (ref "X4") (pin "A9") (pinfunction "A9_A9") (pintype "passive"))
      (node (ref "X4") (pin "B1") (pinfunction "B1_B1") (pintype "passive"))
      (node (ref "X4") (pin "B11") (pinfunction "B11_B11") (pintype "passive"))
      (node (ref "X4") (pin "B16") (pinfunction "B16_B16") (pintype "passive"))
      (node (ref "X4") (pin "B18") (pinfunction "B18_B18") (pintype "passive"))
      (node (ref "X4") (pin "B28") (pinfunction "B28_B28") (pintype "passive"))
      (node (ref "X4") (pin "B32") (pinfunction "B32_B32") (pintype "passive"))
      (node (ref "X4") (pin "B9") (pinfunction "B9_B9") (pintype "passive"))
      (node (ref "X5") (pin "A1") (pinfunction "A1_A1") (pintype "passive"))
      (node (ref "X5") (pin "A11") (pinfunction "A11_A11") (pintype "passive"))
      (node (ref "X5") (pin "A16") (pinfunction "A16_A16") (pintype "passive"))
      (node (ref "X5") (pin "A18") (pinfunction "A18_A18") (pintype "passive"))
      (node (ref "X5") (pin "A28") (pinfunction "A28_A28") (pintype "passive"))
      (node (ref "X5") (pin "A32") (pinfunction "A32_A32") (pintype "passive"))
      (node (ref "X5") (pin "A9") (pinfunction "A9_A9") (pintype "passive"))
      (node (ref "X5") (pin "B1") (pinfunction "B1_B1") (pintype "passive"))
      (node (ref "X5") (pin "B11") (pinfunction "B11_B11") (pintype "passive"))
      (node (ref "X5") (pin "B16") (pinfunction "B16_B16") (pintype "passive"))
      (node (ref "X5") (pin "B18") (pinfunction "B18_B18") (pintype "passive"))
      (node (ref "X5") (pin "B28") (pinfunction "B28_B28") (pintype "passive"))
      (node (ref "X5") (pin "B32") (pinfunction "B32_B32") (pintype "passive"))
      (node (ref "X5") (pin "B9") (pinfunction "B9_B9") (pintype "passive"))
      (node (ref "X6") (pin "A1") (pinfunction "A1_A1") (pintype "passive"))
      (node (ref "X6") (pin "A11") (pinfunction "A11_A11") (pintype "passive"))
      (node (ref "X6") (pin "A16") (pinfunction "A16_A16") (pintype "passive"))
      (node (ref "X6") (pin "A18") (pinfunction "A18_A18") (pintype "passive"))
      (node (ref "X6") (pin "A28") (pinfunction "A28_A28") (pintype "passive"))
      (node (ref "X6") (pin "A32") (pinfunction "A32_A32") (pintype "passive"))
      (node (ref "X6") (pin "A9") (pinfunction "A9_A9") (pintype "passive"))
      (node (ref "X6") (pin "B1") (pinfunction "B1_B1") (pintype "passive"))
      (node (ref "X6") (pin "B11") (pinfunction "B11_B11") (pintype "passive"))
      (node (ref "X6") (pin "B16") (pinfunction "B16_B16") (pintype "passive"))
      (node (ref "X6") (pin "B18") (pinfunction "B18_B18") (pintype "passive"))
      (node (ref "X6") (pin "B28") (pinfunction "B28_B28") (pintype "passive"))
      (node (ref "X6") (pin "B32") (pinfunction "B32_B32") (pintype "passive"))
      (node (ref "X6") (pin "B9") (pinfunction "B9_B9") (pintype "passive"))
      (node (ref "X7") (pin "A1") (pinfunction "A1_A1") (pintype "passive"))
      (node (ref "X7") (pin "A11") (pinfunction "A11_A11") (pintype "passive"))
      (node (ref "X7") (pin "A16") (pinfunction "A16_A16") (pintype "passive"))
      (node (ref "X7") (pin "A18") (pinfunction "A18_A18") (pintype "passive"))
      (node (ref "X7") (pin "A28") (pinfunction "A28_A28") (pintype "passive"))
      (node (ref "X7") (pin "A32") (pinfunction "A32_A32") (pintype "passive"))
      (node (ref "X7") (pin "A9") (pinfunction "A9_A9") (pintype "passive"))
      (node (ref "X7") (pin "B1") (pinfunction "B1_B1") (pintype "passive"))
      (node (ref "X7") (pin "B11") (pinfunction "B11_B11") (pintype "passive"))
      (node (ref "X7") (pin "B16") (pinfunction "B16_B16") (pintype "passive"))
      (node (ref "X7") (pin "B18") (pinfunction "B18_B18") (pintype "passive"))
      (node (ref "X7") (pin "B28") (pinfunction "B28_B28") (pintype "passive"))
      (node (ref "X7") (pin "B32") (pinfunction "B32_B32") (pintype "passive"))
      (node (ref "X7") (pin "B9") (pinfunction "B9_B9") (pintype "passive"))
      (node (ref "X8") (pin "A1") (pinfunction "A1_A1") (pintype "passive"))
      (node (ref "X8") (pin "A11") (pinfunction "A11_A11") (pintype "passive"))
      (node (ref "X8") (pin "A16") (pinfunction "A16_A16") (pintype "passive"))
      (node (ref "X8") (pin "A18") (pinfunction "A18_A18") (pintype "passive"))
      (node (ref "X8") (pin "A28") (pinfunction "A28_A28") (pintype "passive"))
      (node (ref "X8") (pin "A32") (pinfunction "A32_A32") (pintype "passive"))
      (node (ref "X8") (pin "A9") (pinfunction "A9_A9") (pintype "passive"))
      (node (ref "X8") (pin "B1") (pinfunction "B1_B1") (pintype "passive"))
      (node (ref "X8") (pin "B11") (pinfunction "B11_B11") (pintype "passive"))
      (node (ref "X8") (pin "B16") (pinfunction "B16_B16") (pintype "passive"))
      (node (ref "X8") (pin "B18") (pinfunction "B18_B18") (pintype "passive"))
      (node (ref "X8") (pin "B28") (pinfunction "B28_B28") (pintype "passive"))
      (node (ref "X8") (pin "B32") (pinfunction "B32_B32") (pintype "passive"))
      (node (ref "X8") (pin "B9") (pinfunction "B9_B9") (pintype "passive"))
      (node (ref "X9") (pin "A1") (pinfunction "A1_A1") (pintype "passive"))
      (node (ref "X9") (pin "A11") (pinfunction "A11_A11") (pintype "passive"))
      (node (ref "X9") (pin "A16") (pinfunction "A16_A16") (pintype "passive"))
      (node (ref "X9") (pin "A18") (pinfunction "A18_A18") (pintype "passive"))
      (node (ref "X9") (pin "A28") (pinfunction "A28_A28") (pintype "passive"))
      (node (ref "X9") (pin "A32") (pinfunction "A32_A32") (pintype "passive"))
      (node (ref "X9") (pin "A9") (pinfunction "A9_A9") (pintype "passive"))
      (node (ref "X9") (pin "B1") (pinfunction "B1_B1") (pintype "passive"))
      (node (ref "X9") (pin "B11") (pinfunction "B11_B11") (pintype "passive"))
      (node (ref "X9") (pin "B16") (pinfunction "B16_B16") (pintype "passive"))
      (node (ref "X9") (pin "B18") (pinfunction "B18_B18") (pintype "passive"))
      (node (ref "X9") (pin "B28") (pinfunction "B28_B28") (pintype "passive"))
      (node (ref "X9") (pin "B32") (pinfunction "B32_B32") (pintype "passive"))
      (node (ref "X9") (pin "B9") (pinfunction "B9_B9") (pintype "passive"))
    )
    (net (code "6") (name "AN0") (class "Default")
      (node (ref "X1") (pin "A29") (pinfunction "A29_A29") (pintype "passive"))
      (node (ref "X10") (pin "A29") (pinfunction "A29_A29") (pintype "passive"))
      (node (ref "X11") (pin "A29") (pinfunction "A29_A29") (pintype "passive"))
      (node (ref "X12") (pin "A29") (pinfunction "A29_A29") (pintype "passive"))
      (node (ref "X13") (pin "A29") (pinfunction "A29_A29") (pintype "passive"))
      (node (ref "X14") (pin "A29") (pinfunction "A29_A29") (pintype "passive"))
      (node (ref "X15") (pin "A29") (pinfunction "A29_A29") (pintype "passive"))
      (node (ref "X16") (pin "A29") (pinfunction "A29_A29") (pintype "passive"))
      (node (ref "X17") (pin "A29") (pinfunction "A29_A29") (pintype "passive"))
      (node (ref "X18") (pin "A29") (pinfunction "A29_A29") (pintype "passive"))
      (node (ref "X19") (pin "A29") (pinfunction "A29_A29") (pintype "passive"))
      (node (ref "X2") (pin "A29") (pinfunction "A29_A29") (pintype "passive"))
      (node (ref "X20") (pin "A29") (pinfunction "A29_A29") (pintype "passive"))
      (node (ref "X3") (pin "A29") (pinfunction "A29_A29") (pintype "passive"))
      (node (ref "X4") (pin "A29") (pinfunction "A29_A29") (pintype "passive"))
      (node (ref "X5") (pin "A29") (pinfunction "A29_A29") (pintype "passive"))
      (node (ref "X6") (pin "A29") (pinfunction "A29_A29") (pintype "passive"))
      (node (ref "X7") (pin "A29") (pinfunction "A29_A29") (pintype "passive"))
      (node (ref "X8") (pin "A29") (pinfunction "A29_A29") (pintype "passive"))
      (node (ref "X9") (pin "A29") (pinfunction "A29_A29") (pintype "passive"))
    )
    (net (code "7") (name "AN1") (class "Default")
      (node (ref "X1") (pin "B29") (pinfunction "B29_B29") (pintype "passive"))
      (node (ref "X10") (pin "B29") (pinfunction "B29_B29") (pintype "passive"))
      (node (ref "X11") (pin "B29") (pinfunction "B29_B29") (pintype "passive"))
      (node (ref "X12") (pin "B29") (pinfunction "B29_B29") (pintype "passive"))
      (node (ref "X13") (pin "B29") (pinfunction "B29_B29") (pintype "passive"))
      (node (ref "X14") (pin "B29") (pinfunction "B29_B29") (pintype "passive"))
      (node (ref "X15") (pin "B29") (pinfunction "B29_B29") (pintype "passive"))
      (node (ref "X16") (pin "B29") (pinfunction "B29_B29") (pintype "passive"))
      (node (ref "X17") (pin "B29") (pinfunction "B29_B29") (pintype "passive"))
      (node (ref "X18") (pin "B29") (pinfunction "B29_B29") (pintype "passive"))
      (node (ref "X19") (pin "B29") (pinfunction "B29_B29") (pintype "passive"))
      (node (ref "X2") (pin "B29") (pinfunction "B29_B29") (pintype "passive"))
      (node (ref "X20") (pin "B29") (pinfunction "B29_B29") (pintype "passive"))
      (node (ref "X3") (pin "B29") (pinfunction "B29_B29") (pintype "passive"))
      (node (ref "X4") (pin "B29") (pinfunction "B29_B29") (pintype "passive"))
      (node (ref "X5") (pin "B29") (pinfunction "B29_B29") (pintype "passive"))
      (node (ref "X6") (pin "B29") (pinfunction "B29_B29") (pintype "passive"))
      (node (ref "X7") (pin "B29") (pinfunction "B29_B29") (pintype "passive"))
      (node (ref "X8") (pin "B29") (pinfunction "B29_B29") (pintype "passive"))
      (node (ref "X9") (pin "B29") (pinfunction "B29_B29") (pintype "passive"))
    )
    (net (code "8") (name "AN2") (class "Default")
      (node (ref "X1") (pin "A30") (pinfunction "A30_A30") (pintype "passive"))
      (node (ref "X10") (pin "A30") (pinfunction "A30_A30") (pintype "passive"))
      (node (ref "X11") (pin "A30") (pinfunction "A30_A30") (pintype "passive"))
      (node (ref "X12") (pin "A30") (pinfunction "A30_A30") (pintype "passive"))
      (node (ref "X13") (pin "A30") (pinfunction "A30_A30") (pintype "passive"))
      (node (ref "X14") (pin "A30") (pinfunction "A30_A30") (pintype "passive"))
      (node (ref "X15") (pin "A30") (pinfunction "A30_A30") (pintype "passive"))
      (node (ref "X16") (pin "A30") (pinfunction "A30_A30") (pintype "passive"))
      (node (ref "X17") (pin "A30") (pinfunction "A30_A30") (pintype "passive"))
      (node (ref "X18") (pin "A30") (pinfunction "A30_A30") (pintype "passive"))
      (node (ref "X19") (pin "A30") (pinfunction "A30_A30") (pintype "passive"))
      (node (ref "X2") (pin "A30") (pinfunction "A30_A30") (pintype "passive"))
      (node (ref "X20") (pin "A30") (pinfunction "A30_A30") (pintype "passive"))
      (node (ref "X3") (pin "A30") (pinfunction "A30_A30") (pintype "passive"))
      (node (ref "X4") (pin "A30") (pinfunction "A30_A30") (pintype "passive"))
      (node (ref "X5") (pin "A30") (pinfunction "A30_A30") (pintype "passive"))
      (node (ref "X6") (pin "A30") (pinfunction "A30_A30") (pintype "passive"))
      (node (ref "X7") (pin "A30") (pinfunction "A30_A30") (pintype "passive"))
      (node (ref "X8") (pin "A30") (pinfunction "A30_A30") (pintype "passive"))
      (node (ref "X9") (pin "A30") (pinfunction "A30_A30") (pintype "passive"))
    )
    (net (code "9") (name "AN3") (class "Default")
      (node (ref "X1") (pin "B30") (pinfunction "B30_B30") (pintype "passive"))
      (node (ref "X10") (pin "B30") (pinfunction "B30_B30") (pintype "passive"))
      (node (ref "X11") (pin "B30") (pinfunction "B30_B30") (pintype "passive"))
      (node (ref "X12") (pin "B30") (pinfunction "B30_B30") (pintype "passive"))
      (node (ref "X13") (pin "B30") (pinfunction "B30_B30") (pintype "passive"))
      (node (ref "X14") (pin "B30") (pinfunction "B30_B30") (pintype "passive"))
      (node (ref "X15") (pin "B30") (pinfunction "B30_B30") (pintype "passive"))
      (node (ref "X16") (pin "B30") (pinfunction "B30_B30") (pintype "passive"))
      (node (ref "X17") (pin "B30") (pinfunction "B30_B30") (pintype "passive"))
      (node (ref "X18") (pin "B30") (pinfunction "B30_B30") (pintype "passive"))
      (node (ref "X19") (pin "B30") (pinfunction "B30_B30") (pintype "passive"))
      (node (ref "X2") (pin "B30") (pinfunction "B30_B30") (pintype "passive"))
      (node (ref "X20") (pin "B30") (pinfunction "B30_B30") (pintype "passive"))
      (node (ref "X3") (pin "B30") (pinfunction "B30_B30") (pintype "passive"))
      (node (ref "X4") (pin "B30") (pinfunction "B30_B30") (pintype "passive"))
      (node (ref "X5") (pin "B30") (pinfunction "B30_B30") (pintype "passive"))
      (node (ref "X6") (pin "B30") (pinfunction "B30_B30") (pintype "passive"))
      (node (ref "X7") (pin "B30") (pinfunction "B30_B30") (pintype "passive"))
      (node (ref "X8") (pin "B30") (pinfunction "B30_B30") (pintype "passive"))
      (node (ref "X9") (pin "B30") (pinfunction "B30_B30") (pintype "passive"))
    )
    (net (code "10") (name "AN4") (class "Default")
      (node (ref "X1") (pin "A31") (pinfunction "A31_A31") (pintype "passive"))
      (node (ref "X10") (pin "A31") (pinfunction "A31_A31") (pintype "passive"))
      (node (ref "X11") (pin "A31") (pinfunction "A31_A31") (pintype "passive"))
      (node (ref "X12") (pin "A31") (pinfunction "A31_A31") (pintype "passive"))
      (node (ref "X13") (pin "A31") (pinfunction "A31_A31") (pintype "passive"))
      (node (ref "X14") (pin "A31") (pinfunction "A31_A31") (pintype "passive"))
      (node (ref "X15") (pin "A31") (pinfunction "A31_A31") (pintype "passive"))
      (node (ref "X16") (pin "A31") (pinfunction "A31_A31") (pintype "passive"))
      (node (ref "X17") (pin "A31") (pinfunction "A31_A31") (pintype "passive"))
      (node (ref "X18") (pin "A31") (pinfunction "A31_A31") (pintype "passive"))
      (node (ref "X19") (pin "A31") (pinfunction "A31_A31") (pintype "passive"))
      (node (ref "X2") (pin "A31") (pinfunction "A31_A31") (pintype "passive"))
      (node (ref "X20") (pin "A31") (pinfunction "A31_A31") (pintype "passive"))
      (node (ref "X3") (pin "A31") (pinfunction "A31_A31") (pintype "passive"))
      (node (ref "X4") (pin "A31") (pinfunction "A31_A31") (pintype "passive"))
      (node (ref "X5") (pin "A31") (pinfunction "A31_A31") (pintype "passive"))
      (node (ref "X6") (pin "A31") (pinfunction "A31_A31") (pintype "passive"))
      (node (ref "X7") (pin "A31") (pinfunction "A31_A31") (pintype "passive"))
      (node (ref "X8") (pin "A31") (pinfunction "A31_A31") (pintype "passive"))
      (node (ref "X9") (pin "A31") (pinfunction "A31_A31") (pintype "passive"))
    )
    (net (code "11") (name "AN5") (class "Default")
      (node (ref "X1") (pin "B31") (pinfunction "B31_B31") (pintype "passive"))
      (node (ref "X10") (pin "B31") (pinfunction "B31_B31") (pintype "passive"))
      (node (ref "X11") (pin "B31") (pinfunction "B31_B31") (pintype "passive"))
      (node (ref "X12") (pin "B31") (pinfunction "B31_B31") (pintype "passive"))
      (node (ref "X13") (pin "B31") (pinfunction "B31_B31") (pintype "passive"))
      (node (ref "X14") (pin "B31") (pinfunction "B31_B31") (pintype "passive"))
      (node (ref "X15") (pin "B31") (pinfunction "B31_B31") (pintype "passive"))
      (node (ref "X16") (pin "B31") (pinfunction "B31_B31") (pintype "passive"))
      (node (ref "X17") (pin "B31") (pinfunction "B31_B31") (pintype "passive"))
      (node (ref "X18") (pin "B31") (pinfunction "B31_B31") (pintype "passive"))
      (node (ref "X19") (pin "B31") (pinfunction "B31_B31") (pintype "passive"))
      (node (ref "X2") (pin "B31") (pinfunction "B31_B31") (pintype "passive"))
      (node (ref "X20") (pin "B31") (pinfunction "B31_B31") (pintype "passive"))
      (node (ref "X3") (pin "B31") (pinfunction "B31_B31") (pintype "passive"))
      (node (ref "X4") (pin "B31") (pinfunction "B31_B31") (pintype "passive"))
      (node (ref "X5") (pin "B31") (pinfunction "B31_B31") (pintype "passive"))
      (node (ref "X6") (pin "B31") (pinfunction "B31_B31") (pintype "passive"))
      (node (ref "X7") (pin "B31") (pinfunction "B31_B31") (pintype "passive"))
      (node (ref "X8") (pin "B31") (pinfunction "B31_B31") (pintype "passive"))
      (node (ref "X9") (pin "B31") (pinfunction "B31_B31") (pintype "passive"))
    )
    (net (code "12") (name "GND") (class "Default")
      (node (ref "SJ1") (pin "2") (pinfunction "2_2") (pintype "passive"))
      (node (ref "X1") (pin "A2") (pinfunction "A2_A2") (pintype "passive"))
      (node (ref "X1") (pin "A26") (pinfunction "A26_A26") (pintype "passive"))
      (node (ref "X1") (pin "A3") (pinfunction "A3_A3") (pintype "passive"))
      (node (ref "X1") (pin "B19") (pinfunction "B19_B19") (pintype "passive"))
      (node (ref "X1") (pin "B2") (pinfunction "B2_B2") (pintype "passive"))
      (node (ref "X1") (pin "B20") (pinfunction "B20_B20") (pintype "passive"))
      (node (ref "X1") (pin "B21") (pinfunction "B21_B21") (pintype "passive"))
      (node (ref "X1") (pin "B22") (pinfunction "B22_B22") (pintype "passive"))
      (node (ref "X1") (pin "B23") (pinfunction "B23_B23") (pintype "passive"))
      (node (ref "X1") (pin "B24") (pinfunction "B24_B24") (pintype "passive"))
      (node (ref "X1") (pin "B25") (pinfunction "B25_B25") (pintype "passive"))
      (node (ref "X1") (pin "B26") (pinfunction "B26_B26") (pintype "passive"))
      (node (ref "X1") (pin "B3") (pinfunction "B3_B3") (pintype "passive"))
      (node (ref "X10") (pin "A2") (pinfunction "A2_A2") (pintype "passive"))
      (node (ref "X10") (pin "A26") (pinfunction "A26_A26") (pintype "passive"))
      (node (ref "X10") (pin "A3") (pinfunction "A3_A3") (pintype "passive"))
      (node (ref "X10") (pin "B19") (pinfunction "B19_B19") (pintype "passive"))
      (node (ref "X10") (pin "B2") (pinfunction "B2_B2") (pintype "passive"))
      (node (ref "X10") (pin "B20") (pinfunction "B20_B20") (pintype "passive"))
      (node (ref "X10") (pin "B21") (pinfunction "B21_B21") (pintype "passive"))
      (node (ref "X10") (pin "B22") (pinfunction "B22_B22") (pintype "passive"))
      (node (ref "X10") (pin "B23") (pinfunction "B23_B23") (pintype "passive"))
      (node (ref "X10") (pin "B24") (pinfunction "B24_B24") (pintype "passive"))
      (node (ref "X10") (pin "B25") (pinfunction "B25_B25") (pintype "passive"))
      (node (ref "X10") (pin "B26") (pinfunction "B26_B26") (pintype "passive"))
      (node (ref "X10") (pin "B3") (pinfunction "B3_B3") (pintype "passive"))
      (node (ref "X11") (pin "A2") (pinfunction "A2_A2") (pintype "passive"))
      (node (ref "X11") (pin "A26") (pinfunction "A26_A26") (pintype "passive"))
      (node (ref "X11") (pin "A3") (pinfunction "A3_A3") (pintype "passive"))
      (node (ref "X11") (pin "B19") (pinfunction "B19_B19") (pintype "passive"))
      (node (ref "X11") (pin "B2") (pinfunction "B2_B2") (pintype "passive"))
      (node (ref "X11") (pin "B20") (pinfunction "B20_B20") (pintype "passive"))
      (node (ref "X11") (pin "B21") (pinfunction "B21_B21") (pintype "passive"))
      (node (ref "X11") (pin "B22") (pinfunction "B22_B22") (pintype "passive"))
      (node (ref "X11") (pin "B23") (pinfunction "B23_B23") (pintype "passive"))
      (node (ref "X11") (pin "B24") (pinfunction "B24_B24") (pintype "passive"))
      (node (ref "X11") (pin "B25") (pinfunction "B25_B25") (pintype "passive"))
      (node (ref "X11") (pin "B26") (pinfunction "B26_B26") (pintype "passive"))
      (node (ref "X11") (pin "B3") (pinfunction "B3_B3") (pintype "passive"))
      (node (ref "X12") (pin "A2") (pinfunction "A2_A2") (pintype "passive"))
      (node (ref "X12") (pin "A26") (pinfunction "A26_A26") (pintype "passive"))
      (node (ref "X12") (pin "A3") (pinfunction "A3_A3") (pintype "passive"))
      (node (ref "X12") (pin "B19") (pinfunction "B19_B19") (pintype "passive"))
      (node (ref "X12") (pin "B2") (pinfunction "B2_B2") (pintype "passive"))
      (node (ref "X12") (pin "B20") (pinfunction "B20_B20") (pintype "passive"))
      (node (ref "X12") (pin "B21") (pinfunction "B21_B21") (pintype "passive"))
      (node (ref "X12") (pin "B22") (pinfunction "B22_B22") (pintype "passive"))
      (node (ref "X12") (pin "B23") (pinfunction "B23_B23") (pintype "passive"))
      (node (ref "X12") (pin "B24") (pinfunction "B24_B24") (pintype "passive"))
      (node (ref "X12") (pin "B25") (pinfunction "B25_B25") (pintype "passive"))
      (node (ref "X12") (pin "B26") (pinfunction "B26_B26") (pintype "passive"))
      (node (ref "X12") (pin "B3") (pinfunction "B3_B3") (pintype "passive"))
      (node (ref "X13") (pin "A2") (pinfunction "A2_A2") (pintype "passive"))
      (node (ref "X13") (pin "A26") (pinfunction "A26_A26") (pintype "passive"))
      (node (ref "X13") (pin "A3") (pinfunction "A3_A3") (pintype "passive"))
      (node (ref "X13") (pin "B19") (pinfunction "B19_B19") (pintype "passive"))
      (node (ref "X13") (pin "B2") (pinfunction "B2_B2") (pintype "passive"))
      (node (ref "X13") (pin "B20") (pinfunction "B20_B20") (pintype "passive"))
      (node (ref "X13") (pin "B21") (pinfunction "B21_B21") (pintype "passive"))
      (node (ref "X13") (pin "B22") (pinfunction "B22_B22") (pintype "passive"))
      (node (ref "X13") (pin "B23") (pinfunction "B23_B23") (pintype "passive"))
      (node (ref "X13") (pin "B24") (pinfunction "B24_B24") (pintype "passive"))
      (node (ref "X13") (pin "B25") (pinfunction "B25_B25") (pintype "passive"))
      (node (ref "X13") (pin "B26") (pinfunction "B26_B26") (pintype "passive"))
      (node (ref "X13") (pin "B3") (pinfunction "B3_B3") (pintype "passive"))
      (node (ref "X14") (pin "A2") (pinfunction "A2_A2") (pintype "passive"))
      (node (ref "X14") (pin "A26") (pinfunction "A26_A26") (pintype "passive"))
      (node (ref "X14") (pin "A3") (pinfunction "A3_A3") (pintype "passive"))
      (node (ref "X14") (pin "B19") (pinfunction "B19_B19") (pintype "passive"))
      (node (ref "X14") (pin "B2") (pinfunction "B2_B2") (pintype "passive"))
      (node (ref "X14") (pin "B20") (pinfunction "B20_B20") (pintype "passive"))
      (node (ref "X14") (pin "B21") (pinfunction "B21_B21") (pintype "passive"))
      (node (ref "X14") (pin "B22") (pinfunction "B22_B22") (pintype "passive"))
      (node (ref "X14") (pin "B23") (pinfunction "B23_B23") (pintype "passive"))
      (node (ref "X14") (pin "B24") (pinfunction "B24_B24") (pintype "passive"))
      (node (ref "X14") (pin "B25") (pinfunction "B25_B25") (pintype "passive"))
      (node (ref "X14") (pin "B26") (pinfunction "B26_B26") (pintype "passive"))
      (node (ref "X14") (pin "B3") (pinfunction "B3_B3") (pintype "passive"))
      (node (ref "X15") (pin "A2") (pinfunction "A2_A2") (pintype "passive"))
      (node (ref "X15") (pin "A26") (pinfunction "A26_A26") (pintype "passive"))
      (node (ref "X15") (pin "A3") (pinfunction "A3_A3") (pintype "passive"))
      (node (ref "X15") (pin "B19") (pinfunction "B19_B19") (pintype "passive"))
      (node (ref "X15") (pin "B2") (pinfunction "B2_B2") (pintype "passive"))
      (node (ref "X15") (pin "B20") (pinfunction "B20_B20") (pintype "passive"))
      (node (ref "X15") (pin "B21") (pinfunction "B21_B21") (pintype "passive"))
      (node (ref "X15") (pin "B22") (pinfunction "B22_B22") (pintype "passive"))
      (node (ref "X15") (pin "B23") (pinfunction "B23_B23") (pintype "passive"))
      (node (ref "X15") (pin "B24") (pinfunction "B24_B24") (pintype "passive"))
      (node (ref "X15") (pin "B25") (pinfunction "B25_B25") (pintype "passive"))
      (node (ref "X15") (pin "B26") (pinfunction "B26_B26") (pintype "passive"))
      (node (ref "X15") (pin "B3") (pinfunction "B3_B3") (pintype "passive"))
      (node (ref "X16") (pin "A2") (pinfunction "A2_A2") (pintype "passive"))
      (node (ref "X16") (pin "A26") (pinfunction "A26_A26") (pintype "passive"))
      (node (ref "X16") (pin "A3") (pinfunction "A3_A3") (pintype "passive"))
      (node (ref "X16") (pin "B19") (pinfunction "B19_B19") (pintype "passive"))
      (node (ref "X16") (pin "B2") (pinfunction "B2_B2") (pintype "passive"))
      (node (ref "X16") (pin "B20") (pinfunction "B20_B20") (pintype "passive"))
      (node (ref "X16") (pin "B21") (pinfunction "B21_B21") (pintype "passive"))
      (node (ref "X16") (pin "B22") (pinfunction "B22_B22") (pintype "passive"))
      (node (ref "X16") (pin "B23") (pinfunction "B23_B23") (pintype "passive"))
      (node (ref "X16") (pin "B24") (pinfunction "B24_B24") (pintype "passive"))
      (node (ref "X16") (pin "B25") (pinfunction "B25_B25") (pintype "passive"))
      (node (ref "X16") (pin "B26") (pinfunction "B26_B26") (pintype "passive"))
      (node (ref "X16") (pin "B3") (pinfunction "B3_B3") (pintype "passive"))
      (node (ref "X17") (pin "A2") (pinfunction "A2_A2") (pintype "passive"))
      (node (ref "X17") (pin "A26") (pinfunction "A26_A26") (pintype "passive"))
      (node (ref "X17") (pin "A3") (pinfunction "A3_A3") (pintype "passive"))
      (node (ref "X17") (pin "B19") (pinfunction "B19_B19") (pintype "passive"))
      (node (ref "X17") (pin "B2") (pinfunction "B2_B2") (pintype "passive"))
      (node (ref "X17") (pin "B20") (pinfunction "B20_B20") (pintype "passive"))
      (node (ref "X17") (pin "B21") (pinfunction "B21_B21") (pintype "passive"))
      (node (ref "X17") (pin "B22") (pinfunction "B22_B22") (pintype "passive"))
      (node (ref "X17") (pin "B23") (pinfunction "B23_B23") (pintype "passive"))
      (node (ref "X17") (pin "B24") (pinfunction "B24_B24") (pintype "passive"))
      (node (ref "X17") (pin "B25") (pinfunction "B25_B25") (pintype "passive"))
      (node (ref "X17") (pin "B26") (pinfunction "B26_B26") (pintype "passive"))
      (node (ref "X17") (pin "B3") (pinfunction "B3_B3") (pintype "passive"))
      (node (ref "X18") (pin "A2") (pinfunction "A2_A2") (pintype "passive"))
      (node (ref "X18") (pin "A26") (pinfunction "A26_A26") (pintype "passive"))
      (node (ref "X18") (pin "A3") (pinfunction "A3_A3") (pintype "passive"))
      (node (ref "X18") (pin "B19") (pinfunction "B19_B19") (pintype "passive"))
      (node (ref "X18") (pin "B2") (pinfunction "B2_B2") (pintype "passive"))
      (node (ref "X18") (pin "B20") (pinfunction "B20_B20") (pintype "passive"))
      (node (ref "X18") (pin "B21") (pinfunction "B21_B21") (pintype "passive"))
      (node (ref "X18") (pin "B22") (pinfunction "B22_B22") (pintype "passive"))
      (node (ref "X18") (pin "B23") (pinfunction "B23_B23") (pintype "passive"))
      (node (ref "X18") (pin "B24") (pinfunction "B24_B24") (pintype "passive"))
      (node (ref "X18") (pin "B25") (pinfunction "B25_B25") (pintype "passive"))
      (node (ref "X18") (pin "B26") (pinfunction "B26_B26") (pintype "passive"))
      (node (ref "X18") (pin "B3") (pinfunction "B3_B3") (pintype "passive"))
      (node (ref "X19") (pin "A2") (pinfunction "A2_A2") (pintype "passive"))
      (node (ref "X19") (pin "A26") (pinfunction "A26_A26") (pintype "passive"))
      (node (ref "X19") (pin "A3") (pinfunction "A3_A3") (pintype "passive"))
      (node (ref "X19") (pin "B19") (pinfunction "B19_B19") (pintype "passive"))
      (node (ref "X19") (pin "B2") (pinfunction "B2_B2") (pintype "passive"))
      (node (ref "X19") (pin "B20") (pinfunction "B20_B20") (pintype "passive"))
      (node (ref "X19") (pin "B21") (pinfunction "B21_B21") (pintype "passive"))
      (node (ref "X19") (pin "B22") (pinfunction "B22_B22") (pintype "passive"))
      (node (ref "X19") (pin "B23") (pinfunction "B23_B23") (pintype "passive"))
      (node (ref "X19") (pin "B24") (pinfunction "B24_B24") (pintype "passive"))
      (node (ref "X19") (pin "B25") (pinfunction "B25_B25") (pintype "passive"))
      (node (ref "X19") (pin "B26") (pinfunction "B26_B26") (pintype "passive"))
      (node (ref "X19") (pin "B3") (pinfunction "B3_B3") (pintype "passive"))
      (node (ref "X2") (pin "A2") (pinfunction "A2_A2") (pintype "passive"))
      (node (ref "X2") (pin "A26") (pinfunction "A26_A26") (pintype "passive"))
      (node (ref "X2") (pin "A3") (pinfunction "A3_A3") (pintype "passive"))
      (node (ref "X2") (pin "B19") (pinfunction "B19_B19") (pintype "passive"))
      (node (ref "X2") (pin "B2") (pinfunction "B2_B2") (pintype "passive"))
      (node (ref "X2") (pin "B20") (pinfunction "B20_B20") (pintype "passive"))
      (node (ref "X2") (pin "B21") (pinfunction "B21_B21") (pintype "passive"))
      (node (ref "X2") (pin "B22") (pinfunction "B22_B22") (pintype "passive"))
      (node (ref "X2") (pin "B23") (pinfunction "B23_B23") (pintype "passive"))
      (node (ref "X2") (pin "B24") (pinfunction "B24_B24") (pintype "passive"))
      (node (ref "X2") (pin "B25") (pinfunction "B25_B25") (pintype "passive"))
      (node (ref "X2") (pin "B26") (pinfunction "B26_B26") (pintype "passive"))
      (node (ref "X2") (pin "B3") (pinfunction "B3_B3") (pintype "passive"))
      (node (ref "X20") (pin "A2") (pinfunction "A2_A2") (pintype "passive"))
      (node (ref "X20") (pin "A26") (pinfunction "A26_A26") (pintype "passive"))
      (node (ref "X20") (pin "A3") (pinfunction "A3_A3") (pintype "passive"))
      (node (ref "X20") (pin "B19") (pinfunction "B19_B19") (pintype "passive"))
      (node (ref "X20") (pin "B2") (pinfunction "B2_B2") (pintype "passive"))
      (node (ref "X20") (pin "B20") (pinfunction "B20_B20") (pintype "passive"))
      (node (ref "X20") (pin "B21") (pinfunction "B21_B21") (pintype "passive"))
      (node (ref "X20") (pin "B22") (pinfunction "B22_B22") (pintype "passive"))
      (node (ref "X20") (pin "B23") (pinfunction "B23_B23") (pintype "passive"))
      (node (ref "X20") (pin "B24") (pinfunction "B24_B24") (pintype "passive"))
      (node (ref "X20") (pin "B25") (pinfunction "B25_B25") (pintype "passive"))
      (node (ref "X20") (pin "B26") (pinfunction "B26_B26") (pintype "passive"))
      (node (ref "X20") (pin "B3") (pinfunction "B3_B3") (pintype "passive"))
      (node (ref "X3") (pin "A2") (pinfunction "A2_A2") (pintype "passive"))
      (node (ref "X3") (pin "A26") (pinfunction "A26_A26") (pintype "passive"))
      (node (ref "X3") (pin "A3") (pinfunction "A3_A3") (pintype "passive"))
      (node (ref "X3") (pin "B19") (pinfunction "B19_B19") (pintype "passive"))
      (node (ref "X3") (pin "B2") (pinfunction "B2_B2") (pintype "passive"))
      (node (ref "X3") (pin "B20") (pinfunction "B20_B20") (pintype "passive"))
      (node (ref "X3") (pin "B21") (pinfunction "B21_B21") (pintype "passive"))
      (node (ref "X3") (pin "B22") (pinfunction "B22_B22") (pintype "passive"))
      (node (ref "X3") (pin "B23") (pinfunction "B23_B23") (pintype "passive"))
      (node (ref "X3") (pin "B24") (pinfunction "B24_B24") (pintype "passive"))
      (node (ref "X3") (pin "B25") (pinfunction "B25_B25") (pintype "passive"))
      (node (ref "X3") (pin "B26") (pinfunction "B26_B26") (pintype "passive"))
      (node (ref "X3") (pin "B3") (pinfunction "B3_B3") (pintype "passive"))
      (node (ref "X4") (pin "A2") (pinfunction "A2_A2") (pintype "passive"))
      (node (ref "X4") (pin "A26") (pinfunction "A26_A26") (pintype "passive"))
      (node (ref "X4") (pin "A3") (pinfunction "A3_A3") (pintype "passive"))
      (node (ref "X4") (pin "B19") (pinfunction "B19_B19") (pintype "passive"))
      (node (ref "X4") (pin "B2") (pinfunction "B2_B2") (pintype "passive"))
      (node (ref "X4") (pin "B20") (pinfunction "B20_B20") (pintype "passive"))
      (node (ref "X4") (pin "B21") (pinfunction "B21_B21") (pintype "passive"))
      (node (ref "X4") (pin "B22") (pinfunction "B22_B22") (pintype "passive"))
      (node (ref "X4") (pin "B23") (pinfunction "B23_B23") (pintype "passive"))
      (node (ref "X4") (pin "B24") (pinfunction "B24_B24") (pintype "passive"))
      (node (ref "X4") (pin "B25") (pinfunction "B25_B25") (pintype "passive"))
      (node (ref "X4") (pin "B26") (pinfunction "B26_B26") (pintype "passive"))
      (node (ref "X4") (pin "B3") (pinfunction "B3_B3") (pintype "passive"))
      (node (ref "X5") (pin "A2") (pinfunction "A2_A2") (pintype "passive"))
      (node (ref "X5") (pin "A26") (pinfunction "A26_A26") (pintype "passive"))
      (node (ref "X5") (pin "A3") (pinfunction "A3_A3") (pintype "passive"))
      (node (ref "X5") (pin "B19") (pinfunction "B19_B19") (pintype "passive"))
      (node (ref "X5") (pin "B2") (pinfunction "B2_B2") (pintype "passive"))
      (node (ref "X5") (pin "B20") (pinfunction "B20_B20") (pintype "passive"))
      (node (ref "X5") (pin "B21") (pinfunction "B21_B21") (pintype "passive"))
      (node (ref "X5") (pin "B22") (pinfunction "B22_B22") (pintype "passive"))
      (node (ref "X5") (pin "B23") (pinfunction "B23_B23") (pintype "passive"))
      (node (ref "X5") (pin "B24") (pinfunction "B24_B24") (pintype "passive"))
      (node (ref "X5") (pin "B25") (pinfunction "B25_B25") (pintype "passive"))
      (node (ref "X5") (pin "B26") (pinfunction "B26_B26") (pintype "passive"))
      (node (ref "X5") (pin "B3") (pinfunction "B3_B3") (pintype "passive"))
      (node (ref "X6") (pin "A2") (pinfunction "A2_A2") (pintype "passive"))
      (node (ref "X6") (pin "A26") (pinfunction "A26_A26") (pintype "passive"))
      (node (ref "X6") (pin "A3") (pinfunction "A3_A3") (pintype "passive"))
      (node (ref "X6") (pin "B19") (pinfunction "B19_B19") (pintype "passive"))
      (node (ref "X6") (pin "B2") (pinfunction "B2_B2") (pintype "passive"))
      (node (ref "X6") (pin "B20") (pinfunction "B20_B20") (pintype "passive"))
      (node (ref "X6") (pin "B21") (pinfunction "B21_B21") (pintype "passive"))
      (node (ref "X6") (pin "B22") (pinfunction "B22_B22") (pintype "passive"))
      (node (ref "X6") (pin "B23") (pinfunction "B23_B23") (pintype "passive"))
      (node (ref "X6") (pin "B24") (pinfunction "B24_B24") (pintype "passive"))
      (node (ref "X6") (pin "B25") (pinfunction "B25_B25") (pintype "passive"))
      (node (ref "X6") (pin "B26") (pinfunction "B26_B26") (pintype "passive"))
      (node (ref "X6") (pin "B3") (pinfunction "B3_B3") (pintype "passive"))
      (node (ref "X7") (pin "A2") (pinfunction "A2_A2") (pintype "passive"))
      (node (ref "X7") (pin "A26") (pinfunction "A26_A26") (pintype "passive"))
      (node (ref "X7") (pin "A3") (pinfunction "A3_A3") (pintype "passive"))
      (node (ref "X7") (pin "B19") (pinfunction "B19_B19") (pintype "passive"))
      (node (ref "X7") (pin "B2") (pinfunction "B2_B2") (pintype "passive"))
      (node (ref "X7") (pin "B20") (pinfunction "B20_B20") (pintype "passive"))
      (node (ref "X7") (pin "B21") (pinfunction "B21_B21") (pintype "passive"))
      (node (ref "X7") (pin "B22") (pinfunction "B22_B22") (pintype "passive"))
      (node (ref "X7") (pin "B23") (pinfunction "B23_B23") (pintype "passive"))
      (node (ref "X7") (pin "B24") (pinfunction "B24_B24") (pintype "passive"))
      (node (ref "X7") (pin "B25") (pinfunction "B25_B25") (pintype "passive"))
      (node (ref "X7") (pin "B26") (pinfunction "B26_B26") (pintype "passive"))
      (node (ref "X7") (pin "B3") (pinfunction "B3_B3") (pintype "passive"))
      (node (ref "X8") (pin "A2") (pinfunction "A2_A2") (pintype "passive"))
      (node (ref "X8") (pin "A26") (pinfunction "A26_A26") (pintype "passive"))
      (node (ref "X8") (pin "A3") (pinfunction "A3_A3") (pintype "passive"))
      (node (ref "X8") (pin "B19") (pinfunction "B19_B19") (pintype "passive"))
      (node (ref "X8") (pin "B2") (pinfunction "B2_B2") (pintype "passive"))
      (node (ref "X8") (pin "B20") (pinfunction "B20_B20") (pintype "passive"))
      (node (ref "X8") (pin "B21") (pinfunction "B21_B21") (pintype "passive"))
      (node (ref "X8") (pin "B22") (pinfunction "B22_B22") (pintype "passive"))
      (node (ref "X8") (pin "B23") (pinfunction "B23_B23") (pintype "passive"))
      (node (ref "X8") (pin "B24") (pinfunction "B24_B24") (pintype "passive"))
      (node (ref "X8") (pin "B25") (pinfunction "B25_B25") (pintype "passive"))
      (node (ref "X8") (pin "B26") (pinfunction "B26_B26") (pintype "passive"))
      (node (ref "X8") (pin "B3") (pinfunction "B3_B3") (pintype "passive"))
      (node (ref "X9") (pin "A2") (pinfunction "A2_A2") (pintype "passive"))
      (node (ref "X9") (pin "A26") (pinfunction "A26_A26") (pintype "passive"))
      (node (ref "X9") (pin "A3") (pinfunction "A3_A3") (pintype "passive"))
      (node (ref "X9") (pin "B19") (pinfunction "B19_B19") (pintype "passive"))
      (node (ref "X9") (pin "B2") (pinfunction "B2_B2") (pintype "passive"))
      (node (ref "X9") (pin "B20") (pinfunction "B20_B20") (pintype "passive"))
      (node (ref "X9") (pin "B21") (pinfunction "B21_B21") (pintype "passive"))
      (node (ref "X9") (pin "B22") (pinfunction "B22_B22") (pintype "passive"))
      (node (ref "X9") (pin "B23") (pinfunction "B23_B23") (pintype "passive"))
      (node (ref "X9") (pin "B24") (pinfunction "B24_B24") (pintype "passive"))
      (node (ref "X9") (pin "B25") (pinfunction "B25_B25") (pintype "passive"))
      (node (ref "X9") (pin "B26") (pinfunction "B26_B26") (pintype "passive"))
      (node (ref "X9") (pin "B3") (pinfunction "B3_B3") (pintype "passive"))
    )
    (net (code "13") (name "GPIO0") (class "Default")
      (node (ref "X1") (pin "A5") (pinfunction "A5_A5") (pintype "passive"))
      (node (ref "X10") (pin "A5") (pinfunction "A5_A5") (pintype "passive"))
      (node (ref "X11") (pin "A5") (pinfunction "A5_A5") (pintype "passive"))
      (node (ref "X12") (pin "A5") (pinfunction "A5_A5") (pintype "passive"))
      (node (ref "X13") (pin "A5") (pinfunction "A5_A5") (pintype "passive"))
      (node (ref "X14") (pin "A5") (pinfunction "A5_A5") (pintype "passive"))
      (node (ref "X15") (pin "A5") (pinfunction "A5_A5") (pintype "passive"))
      (node (ref "X16") (pin "A5") (pinfunction "A5_A5") (pintype "passive"))
      (node (ref "X17") (pin "A5") (pinfunction "A5_A5") (pintype "passive"))
      (node (ref "X18") (pin "A5") (pinfunction "A5_A5") (pintype "passive"))
      (node (ref "X19") (pin "A5") (pinfunction "A5_A5") (pintype "passive"))
      (node (ref "X2") (pin "A5") (pinfunction "A5_A5") (pintype "passive"))
      (node (ref "X20") (pin "A5") (pinfunction "A5_A5") (pintype "passive"))
      (node (ref "X3") (pin "A5") (pinfunction "A5_A5") (pintype "passive"))
      (node (ref "X4") (pin "A5") (pinfunction "A5_A5") (pintype "passive"))
      (node (ref "X5") (pin "A5") (pinfunction "A5_A5") (pintype "passive"))
      (node (ref "X6") (pin "A5") (pinfunction "A5_A5") (pintype "passive"))
      (node (ref "X7") (pin "A5") (pinfunction "A5_A5") (pintype "passive"))
      (node (ref "X8") (pin "A5") (pinfunction "A5_A5") (pintype "passive"))
      (node (ref "X9") (pin "A5") (pinfunction "A5_A5") (pintype "passive"))
    )
    (net (code "14") (name "GPIO1") (class "Default")
      (node (ref "X1") (pin "B5") (pinfunction "B5_B5") (pintype "passive"))
      (node (ref "X10") (pin "B5") (pinfunction "B5_B5") (pintype "passive"))
      (node (ref "X11") (pin "B5") (pinfunction "B5_B5") (pintype "passive"))
      (node (ref "X12") (pin "B5") (pinfunction "B5_B5") (pintype "passive"))
      (node (ref "X13") (pin "B5") (pinfunction "B5_B5") (pintype "passive"))
      (node (ref "X14") (pin "B5") (pinfunction "B5_B5") (pintype "passive"))
      (node (ref "X15") (pin "B5") (pinfunction "B5_B5") (pintype "passive"))
      (node (ref "X16") (pin "B5") (pinfunction "B5_B5") (pintype "passive"))
      (node (ref "X17") (pin "B5") (pinfunction "B5_B5") (pintype "passive"))
      (node (ref "X18") (pin "B5") (pinfunction "B5_B5") (pintype "passive"))
      (node (ref "X19") (pin "B5") (pinfunction "B5_B5") (pintype "passive"))
      (node (ref "X2") (pin "B5") (pinfunction "B5_B5") (pintype "passive"))
      (node (ref "X20") (pin "B5") (pinfunction "B5_B5") (pintype "passive"))
      (node (ref "X3") (pin "B5") (pinfunction "B5_B5") (pintype "passive"))
      (node (ref "X4") (pin "B5") (pinfunction "B5_B5") (pintype "passive"))
      (node (ref "X5") (pin "B5") (pinfunction "B5_B5") (pintype "passive"))
      (node (ref "X6") (pin "B5") (pinfunction "B5_B5") (pintype "passive"))
      (node (ref "X7") (pin "B5") (pinfunction "B5_B5") (pintype "passive"))
      (node (ref "X8") (pin "B5") (pinfunction "B5_B5") (pintype "passive"))
      (node (ref "X9") (pin "B5") (pinfunction "B5_B5") (pintype "passive"))
    )
    (net (code "15") (name "GPIO2") (class "Default")
      (node (ref "X1") (pin "A6") (pinfunction "A6_A6") (pintype "passive"))
      (node (ref "X10") (pin "A6") (pinfunction "A6_A6") (pintype "passive"))
      (node (ref "X11") (pin "A6") (pinfunction "A6_A6") (pintype "passive"))
      (node (ref "X12") (pin "A6") (pinfunction "A6_A6") (pintype "passive"))
      (node (ref "X13") (pin "A6") (pinfunction "A6_A6") (pintype "passive"))
      (node (ref "X14") (pin "A6") (pinfunction "A6_A6") (pintype "passive"))
      (node (ref "X15") (pin "A6") (pinfunction "A6_A6") (pintype "passive"))
      (node (ref "X16") (pin "A6") (pinfunction "A6_A6") (pintype "passive"))
      (node (ref "X17") (pin "A6") (pinfunction "A6_A6") (pintype "passive"))
      (node (ref "X18") (pin "A6") (pinfunction "A6_A6") (pintype "passive"))
      (node (ref "X19") (pin "A6") (pinfunction "A6_A6") (pintype "passive"))
      (node (ref "X2") (pin "A6") (pinfunction "A6_A6") (pintype "passive"))
      (node (ref "X20") (pin "A6") (pinfunction "A6_A6") (pintype "passive"))
      (node (ref "X3") (pin "A6") (pinfunction "A6_A6") (pintype "passive"))
      (node (ref "X4") (pin "A6") (pinfunction "A6_A6") (pintype "passive"))
      (node (ref "X5") (pin "A6") (pinfunction "A6_A6") (pintype "passive"))
      (node (ref "X6") (pin "A6") (pinfunction "A6_A6") (pintype "passive"))
      (node (ref "X7") (pin "A6") (pinfunction "A6_A6") (pintype "passive"))
      (node (ref "X8") (pin "A6") (pinfunction "A6_A6") (pintype "passive"))
      (node (ref "X9") (pin "A6") (pinfunction "A6_A6") (pintype "passive"))
    )
    (net (code "16") (name "GPIO3") (class "Default")
      (node (ref "X1") (pin "B6") (pinfunction "B6_B6") (pintype "passive"))
      (node (ref "X10") (pin "B6") (pinfunction "B6_B6") (pintype "passive"))
      (node (ref "X11") (pin "B6") (pinfunction "B6_B6") (pintype "passive"))
      (node (ref "X12") (pin "B6") (pinfunction "B6_B6") (pintype "passive"))
      (node (ref "X13") (pin "B6") (pinfunction "B6_B6") (pintype "passive"))
      (node (ref "X14") (pin "B6") (pinfunction "B6_B6") (pintype "passive"))
      (node (ref "X15") (pin "B6") (pinfunction "B6_B6") (pintype "passive"))
      (node (ref "X16") (pin "B6") (pinfunction "B6_B6") (pintype "passive"))
      (node (ref "X17") (pin "B6") (pinfunction "B6_B6") (pintype "passive"))
      (node (ref "X18") (pin "B6") (pinfunction "B6_B6") (pintype "passive"))
      (node (ref "X19") (pin "B6") (pinfunction "B6_B6") (pintype "passive"))
      (node (ref "X2") (pin "B6") (pinfunction "B6_B6") (pintype "passive"))
      (node (ref "X20") (pin "B6") (pinfunction "B6_B6") (pintype "passive"))
      (node (ref "X3") (pin "B6") (pinfunction "B6_B6") (pintype "passive"))
      (node (ref "X4") (pin "B6") (pinfunction "B6_B6") (pintype "passive"))
      (node (ref "X5") (pin "B6") (pinfunction "B6_B6") (pintype "passive"))
      (node (ref "X6") (pin "B6") (pinfunction "B6_B6") (pintype "passive"))
      (node (ref "X7") (pin "B6") (pinfunction "B6_B6") (pintype "passive"))
      (node (ref "X8") (pin "B6") (pinfunction "B6_B6") (pintype "passive"))
      (node (ref "X9") (pin "B6") (pinfunction "B6_B6") (pintype "passive"))
    )
    (net (code "17") (name "GPIO4") (class "Default")
      (node (ref "X1") (pin "A7") (pinfunction "A7_A7") (pintype "passive"))
      (node (ref "X10") (pin "A7") (pinfunction "A7_A7") (pintype "passive"))
      (node (ref "X11") (pin "A7") (pinfunction "A7_A7") (pintype "passive"))
      (node (ref "X12") (pin "A7") (pinfunction "A7_A7") (pintype "passive"))
      (node (ref "X13") (pin "A7") (pinfunction "A7_A7") (pintype "passive"))
      (node (ref "X14") (pin "A7") (pinfunction "A7_A7") (pintype "passive"))
      (node (ref "X15") (pin "A7") (pinfunction "A7_A7") (pintype "passive"))
      (node (ref "X16") (pin "A7") (pinfunction "A7_A7") (pintype "passive"))
      (node (ref "X17") (pin "A7") (pinfunction "A7_A7") (pintype "passive"))
      (node (ref "X18") (pin "A7") (pinfunction "A7_A7") (pintype "passive"))
      (node (ref "X19") (pin "A7") (pinfunction "A7_A7") (pintype "passive"))
      (node (ref "X2") (pin "A7") (pinfunction "A7_A7") (pintype "passive"))
      (node (ref "X20") (pin "A7") (pinfunction "A7_A7") (pintype "passive"))
      (node (ref "X3") (pin "A7") (pinfunction "A7_A7") (pintype "passive"))
      (node (ref "X4") (pin "A7") (pinfunction "A7_A7") (pintype "passive"))
      (node (ref "X5") (pin "A7") (pinfunction "A7_A7") (pintype "passive"))
      (node (ref "X6") (pin "A7") (pinfunction "A7_A7") (pintype "passive"))
      (node (ref "X7") (pin "A7") (pinfunction "A7_A7") (pintype "passive"))
      (node (ref "X8") (pin "A7") (pinfunction "A7_A7") (pintype "passive"))
      (node (ref "X9") (pin "A7") (pinfunction "A7_A7") (pintype "passive"))
    )
    (net (code "18") (name "GPIO5") (class "Default")
      (node (ref "X1") (pin "B7") (pinfunction "B7_B7") (pintype "passive"))
      (node (ref "X10") (pin "B7") (pinfunction "B7_B7") (pintype "passive"))
      (node (ref "X11") (pin "B7") (pinfunction "B7_B7") (pintype "passive"))
      (node (ref "X12") (pin "B7") (pinfunction "B7_B7") (pintype "passive"))
      (node (ref "X13") (pin "B7") (pinfunction "B7_B7") (pintype "passive"))
      (node (ref "X14") (pin "B7") (pinfunction "B7_B7") (pintype "passive"))
      (node (ref "X15") (pin "B7") (pinfunction "B7_B7") (pintype "passive"))
      (node (ref "X16") (pin "B7") (pinfunction "B7_B7") (pintype "passive"))
      (node (ref "X17") (pin "B7") (pinfunction "B7_B7") (pintype "passive"))
      (node (ref "X18") (pin "B7") (pinfunction "B7_B7") (pintype "passive"))
      (node (ref "X19") (pin "B7") (pinfunction "B7_B7") (pintype "passive"))
      (node (ref "X2") (pin "B7") (pinfunction "B7_B7") (pintype "passive"))
      (node (ref "X20") (pin "B7") (pinfunction "B7_B7") (pintype "passive"))
      (node (ref "X3") (pin "B7") (pinfunction "B7_B7") (pintype "passive"))
      (node (ref "X4") (pin "B7") (pinfunction "B7_B7") (pintype "passive"))
      (node (ref "X5") (pin "B7") (pinfunction "B7_B7") (pintype "passive"))
      (node (ref "X6") (pin "B7") (pinfunction "B7_B7") (pintype "passive"))
      (node (ref "X7") (pin "B7") (pinfunction "B7_B7") (pintype "passive"))
      (node (ref "X8") (pin "B7") (pinfunction "B7_B7") (pintype "passive"))
      (node (ref "X9") (pin "B7") (pinfunction "B7_B7") (pintype "passive"))
    )
    (net (code "19") (name "GPIO6") (class "Default")
      (node (ref "X1") (pin "A8") (pinfunction "A8_A8") (pintype "passive"))
      (node (ref "X10") (pin "A8") (pinfunction "A8_A8") (pintype "passive"))
      (node (ref "X11") (pin "A8") (pinfunction "A8_A8") (pintype "passive"))
      (node (ref "X12") (pin "A8") (pinfunction "A8_A8") (pintype "passive"))
      (node (ref "X13") (pin "A8") (pinfunction "A8_A8") (pintype "passive"))
      (node (ref "X14") (pin "A8") (pinfunction "A8_A8") (pintype "passive"))
      (node (ref "X15") (pin "A8") (pinfunction "A8_A8") (pintype "passive"))
      (node (ref "X16") (pin "A8") (pinfunction "A8_A8") (pintype "passive"))
      (node (ref "X17") (pin "A8") (pinfunction "A8_A8") (pintype "passive"))
      (node (ref "X18") (pin "A8") (pinfunction "A8_A8") (pintype "passive"))
      (node (ref "X19") (pin "A8") (pinfunction "A8_A8") (pintype "passive"))
      (node (ref "X2") (pin "A8") (pinfunction "A8_A8") (pintype "passive"))
      (node (ref "X20") (pin "A8") (pinfunction "A8_A8") (pintype "passive"))
      (node (ref "X3") (pin "A8") (pinfunction "A8_A8") (pintype "passive"))
      (node (ref "X4") (pin "A8") (pinfunction "A8_A8") (pintype "passive"))
      (node (ref "X5") (pin "A8") (pinfunction "A8_A8") (pintype "passive"))
      (node (ref "X6") (pin "A8") (pinfunction "A8_A8") (pintype "passive"))
      (node (ref "X7") (pin "A8") (pinfunction "A8_A8") (pintype "passive"))
      (node (ref "X8") (pin "A8") (pinfunction "A8_A8") (pintype "passive"))
      (node (ref "X9") (pin "A8") (pinfunction "A8_A8") (pintype "passive"))
    )
    (net (code "20") (name "GPIO7") (class "Default")
      (node (ref "X1") (pin "B8") (pinfunction "B8_B8") (pintype "passive"))
      (node (ref "X10") (pin "B8") (pinfunction "B8_B8") (pintype "passive"))
      (node (ref "X11") (pin "B8") (pinfunction "B8_B8") (pintype "passive"))
      (node (ref "X12") (pin "B8") (pinfunction "B8_B8") (pintype "passive"))
      (node (ref "X13") (pin "B8") (pinfunction "B8_B8") (pintype "passive"))
      (node (ref "X14") (pin "B8") (pinfunction "B8_B8") (pintype "passive"))
      (node (ref "X15") (pin "B8") (pinfunction "B8_B8") (pintype "passive"))
      (node (ref "X16") (pin "B8") (pinfunction "B8_B8") (pintype "passive"))
      (node (ref "X17") (pin "B8") (pinfunction "B8_B8") (pintype "passive"))
      (node (ref "X18") (pin "B8") (pinfunction "B8_B8") (pintype "passive"))
      (node (ref "X19") (pin "B8") (pinfunction "B8_B8") (pintype "passive"))
      (node (ref "X2") (pin "B8") (pinfunction "B8_B8") (pintype "passive"))
      (node (ref "X20") (pin "B8") (pinfunction "B8_B8") (pintype "passive"))
      (node (ref "X3") (pin "B8") (pinfunction "B8_B8") (pintype "passive"))
      (node (ref "X4") (pin "B8") (pinfunction "B8_B8") (pintype "passive"))
      (node (ref "X5") (pin "B8") (pinfunction "B8_B8") (pintype "passive"))
      (node (ref "X6") (pin "B8") (pinfunction "B8_B8") (pintype "passive"))
      (node (ref "X7") (pin "B8") (pinfunction "B8_B8") (pintype "passive"))
      (node (ref "X8") (pin "B8") (pinfunction "B8_B8") (pintype "passive"))
      (node (ref "X9") (pin "B8") (pinfunction "B8_B8") (pintype "passive"))
    )
    (net (code "21") (name "GPIO8") (class "Default")
      (node (ref "X1") (pin "A12") (pinfunction "A12_A12") (pintype "passive"))
      (node (ref "X10") (pin "A12") (pinfunction "A12_A12") (pintype "passive"))
      (node (ref "X11") (pin "A12") (pinfunction "A12_A12") (pintype "passive"))
      (node (ref "X12") (pin "A12") (pinfunction "A12_A12") (pintype "passive"))
      (node (ref "X13") (pin "A12") (pinfunction "A12_A12") (pintype "passive"))
      (node (ref "X14") (pin "A12") (pinfunction "A12_A12") (pintype "passive"))
      (node (ref "X15") (pin "A12") (pinfunction "A12_A12") (pintype "passive"))
      (node (ref "X16") (pin "A12") (pinfunction "A12_A12") (pintype "passive"))
      (node (ref "X17") (pin "A12") (pinfunction "A12_A12") (pintype "passive"))
      (node (ref "X18") (pin "A12") (pinfunction "A12_A12") (pintype "passive"))
      (node (ref "X19") (pin "A12") (pinfunction "A12_A12") (pintype "passive"))
      (node (ref "X2") (pin "A12") (pinfunction "A12_A12") (pintype "passive"))
      (node (ref "X20") (pin "A12") (pinfunction "A12_A12") (pintype "passive"))
      (node (ref "X3") (pin "A12") (pinfunction "A12_A12") (pintype "passive"))
      (node (ref "X4") (pin "A12") (pinfunction "A12_A12") (pintype "passive"))
      (node (ref "X5") (pin "A12") (pinfunction "A12_A12") (pintype "passive"))
      (node (ref "X6") (pin "A12") (pinfunction "A12_A12") (pintype "passive"))
      (node (ref "X7") (pin "A12") (pinfunction "A12_A12") (pintype "passive"))
      (node (ref "X8") (pin "A12") (pinfunction "A12_A12") (pintype "passive"))
      (node (ref "X9") (pin "A12") (pinfunction "A12_A12") (pintype "passive"))
    )
    (net (code "22") (name "GPIO9") (class "Default")
      (node (ref "X1") (pin "B12") (pinfunction "B12_B12") (pintype "passive"))
      (node (ref "X10") (pin "B12") (pinfunction "B12_B12") (pintype "passive"))
      (node (ref "X11") (pin "B12") (pinfunction "B12_B12") (pintype "passive"))
      (node (ref "X12") (pin "B12") (pinfunction "B12_B12") (pintype "passive"))
      (node (ref "X13") (pin "B12") (pinfunction "B12_B12") (pintype "passive"))
      (node (ref "X14") (pin "B12") (pinfunction "B12_B12") (pintype "passive"))
      (node (ref "X15") (pin "B12") (pinfunction "B12_B12") (pintype "passive"))
      (node (ref "X16") (pin "B12") (pinfunction "B12_B12") (pintype "passive"))
      (node (ref "X17") (pin "B12") (pinfunction "B12_B12") (pintype "passive"))
      (node (ref "X18") (pin "B12") (pinfunction "B12_B12") (pintype "passive"))
      (node (ref "X19") (pin "B12") (pinfunction "B12_B12") (pintype "passive"))
      (node (ref "X2") (pin "B12") (pinfunction "B12_B12") (pintype "passive"))
      (node (ref "X20") (pin "B12") (pinfunction "B12_B12") (pintype "passive"))
      (node (ref "X3") (pin "B12") (pinfunction "B12_B12") (pintype "passive"))
      (node (ref "X4") (pin "B12") (pinfunction "B12_B12") (pintype "passive"))
      (node (ref "X5") (pin "B12") (pinfunction "B12_B12") (pintype "passive"))
      (node (ref "X6") (pin "B12") (pinfunction "B12_B12") (pintype "passive"))
      (node (ref "X7") (pin "B12") (pinfunction "B12_B12") (pintype "passive"))
      (node (ref "X8") (pin "B12") (pinfunction "B12_B12") (pintype "passive"))
      (node (ref "X9") (pin "B12") (pinfunction "B12_B12") (pintype "passive"))
    )
    (net (code "23") (name "GPIO10") (class "Default")
      (node (ref "X1") (pin "A13") (pinfunction "A13_A13") (pintype "passive"))
      (node (ref "X10") (pin "A13") (pinfunction "A13_A13") (pintype "passive"))
      (node (ref "X11") (pin "A13") (pinfunction "A13_A13") (pintype "passive"))
      (node (ref "X12") (pin "A13") (pinfunction "A13_A13") (pintype "passive"))
      (node (ref "X13") (pin "A13") (pinfunction "A13_A13") (pintype "passive"))
      (node (ref "X14") (pin "A13") (pinfunction "A13_A13") (pintype "passive"))
      (node (ref "X15") (pin "A13") (pinfunction "A13_A13") (pintype "passive"))
      (node (ref "X16") (pin "A13") (pinfunction "A13_A13") (pintype "passive"))
      (node (ref "X17") (pin "A13") (pinfunction "A13_A13") (pintype "passive"))
      (node (ref "X18") (pin "A13") (pinfunction "A13_A13") (pintype "passive"))
      (node (ref "X19") (pin "A13") (pinfunction "A13_A13") (pintype "passive"))
      (node (ref "X2") (pin "A13") (pinfunction "A13_A13") (pintype "passive"))
      (node (ref "X20") (pin "A13") (pinfunction "A13_A13") (pintype "passive"))
      (node (ref "X3") (pin "A13") (pinfunction "A13_A13") (pintype "passive"))
      (node (ref "X4") (pin "A13") (pinfunction "A13_A13") (pintype "passive"))
      (node (ref "X5") (pin "A13") (pinfunction "A13_A13") (pintype "passive"))
      (node (ref "X6") (pin "A13") (pinfunction "A13_A13") (pintype "passive"))
      (node (ref "X7") (pin "A13") (pinfunction "A13_A13") (pintype "passive"))
      (node (ref "X8") (pin "A13") (pinfunction "A13_A13") (pintype "passive"))
      (node (ref "X9") (pin "A13") (pinfunction "A13_A13") (pintype "passive"))
    )
    (net (code "24") (name "GPIO11") (class "Default")
      (node (ref "X1") (pin "B13") (pinfunction "B13_B13") (pintype "passive"))
      (node (ref "X10") (pin "B13") (pinfunction "B13_B13") (pintype "passive"))
      (node (ref "X11") (pin "B13") (pinfunction "B13_B13") (pintype "passive"))
      (node (ref "X12") (pin "B13") (pinfunction "B13_B13") (pintype "passive"))
      (node (ref "X13") (pin "B13") (pinfunction "B13_B13") (pintype "passive"))
      (node (ref "X14") (pin "B13") (pinfunction "B13_B13") (pintype "passive"))
      (node (ref "X15") (pin "B13") (pinfunction "B13_B13") (pintype "passive"))
      (node (ref "X16") (pin "B13") (pinfunction "B13_B13") (pintype "passive"))
      (node (ref "X17") (pin "B13") (pinfunction "B13_B13") (pintype "passive"))
      (node (ref "X18") (pin "B13") (pinfunction "B13_B13") (pintype "passive"))
      (node (ref "X19") (pin "B13") (pinfunction "B13_B13") (pintype "passive"))
      (node (ref "X2") (pin "B13") (pinfunction "B13_B13") (pintype "passive"))
      (node (ref "X20") (pin "B13") (pinfunction "B13_B13") (pintype "passive"))
      (node (ref "X3") (pin "B13") (pinfunction "B13_B13") (pintype "passive"))
      (node (ref "X4") (pin "B13") (pinfunction "B13_B13") (pintype "passive"))
      (node (ref "X5") (pin "B13") (pinfunction "B13_B13") (pintype "passive"))
      (node (ref "X6") (pin "B13") (pinfunction "B13_B13") (pintype "passive"))
      (node (ref "X7") (pin "B13") (pinfunction "B13_B13") (pintype "passive"))
      (node (ref "X8") (pin "B13") (pinfunction "B13_B13") (pintype "passive"))
      (node (ref "X9") (pin "B13") (pinfunction "B13_B13") (pintype "passive"))
    )
    (net (code "25") (name "GPIO12") (class "Default")
      (node (ref "X1") (pin "A14") (pinfunction "A14_A14") (pintype "passive"))
      (node (ref "X10") (pin "A14") (pinfunction "A14_A14") (pintype "passive"))
      (node (ref "X11") (pin "A14") (pinfunction "A14_A14") (pintype "passive"))
      (node (ref "X12") (pin "A14") (pinfunction "A14_A14") (pintype "passive"))
      (node (ref "X13") (pin "A14") (pinfunction "A14_A14") (pintype "passive"))
      (node (ref "X14") (pin "A14") (pinfunction "A14_A14") (pintype "passive"))
      (node (ref "X15") (pin "A14") (pinfunction "A14_A14") (pintype "passive"))
      (node (ref "X16") (pin "A14") (pinfunction "A14_A14") (pintype "passive"))
      (node (ref "X17") (pin "A14") (pinfunction "A14_A14") (pintype "passive"))
      (node (ref "X18") (pin "A14") (pinfunction "A14_A14") (pintype "passive"))
      (node (ref "X19") (pin "A14") (pinfunction "A14_A14") (pintype "passive"))
      (node (ref "X2") (pin "A14") (pinfunction "A14_A14") (pintype "passive"))
      (node (ref "X20") (pin "A14") (pinfunction "A14_A14") (pintype "passive"))
      (node (ref "X3") (pin "A14") (pinfunction "A14_A14") (pintype "passive"))
      (node (ref "X4") (pin "A14") (pinfunction "A14_A14") (pintype "passive"))
      (node (ref "X5") (pin "A14") (pinfunction "A14_A14") (pintype "passive"))
      (node (ref "X6") (pin "A14") (pinfunction "A14_A14") (pintype "passive"))
      (node (ref "X7") (pin "A14") (pinfunction "A14_A14") (pintype "passive"))
      (node (ref "X8") (pin "A14") (pinfunction "A14_A14") (pintype "passive"))
      (node (ref "X9") (pin "A14") (pinfunction "A14_A14") (pintype "passive"))
    )
    (net (code "26") (name "GPIO13") (class "Default")
      (node (ref "X1") (pin "B14") (pinfunction "B14_B14") (pintype "passive"))
      (node (ref "X10") (pin "B14") (pinfunction "B14_B14") (pintype "passive"))
      (node (ref "X11") (pin "B14") (pinfunction "B14_B14") (pintype "passive"))
      (node (ref "X12") (pin "B14") (pinfunction "B14_B14") (pintype "passive"))
      (node (ref "X13") (pin "B14") (pinfunction "B14_B14") (pintype "passive"))
      (node (ref "X14") (pin "B14") (pinfunction "B14_B14") (pintype "passive"))
      (node (ref "X15") (pin "B14") (pinfunction "B14_B14") (pintype "passive"))
      (node (ref "X16") (pin "B14") (pinfunction "B14_B14") (pintype "passive"))
      (node (ref "X17") (pin "B14") (pinfunction "B14_B14") (pintype "passive"))
      (node (ref "X18") (pin "B14") (pinfunction "B14_B14") (pintype "passive"))
      (node (ref "X19") (pin "B14") (pinfunction "B14_B14") (pintype "passive"))
      (node (ref "X2") (pin "B14") (pinfunction "B14_B14") (pintype "passive"))
      (node (ref "X20") (pin "B14") (pinfunction "B14_B14") (pintype "passive"))
      (node (ref "X3") (pin "B14") (pinfunction "B14_B14") (pintype "passive"))
      (node (ref "X4") (pin "B14") (pinfunction "B14_B14") (pintype "passive"))
      (node (ref "X5") (pin "B14") (pinfunction "B14_B14") (pintype "passive"))
      (node (ref "X6") (pin "B14") (pinfunction "B14_B14") (pintype "passive"))
      (node (ref "X7") (pin "B14") (pinfunction "B14_B14") (pintype "passive"))
      (node (ref "X8") (pin "B14") (pinfunction "B14_B14") (pintype "passive"))
      (node (ref "X9") (pin "B14") (pinfunction "B14_B14") (pintype "passive"))
    )
    (net (code "27") (name "GPIO14") (class "Default")
      (node (ref "X10") (pin "A15") (pinfunction "A15_A15") (pintype "passive"))
      (node (ref "X11") (pin "A15") (pinfunction "A15_A15") (pintype "passive"))
      (node (ref "X12") (pin "A15") (pinfunction "A15_A15") (pintype "passive"))
      (node (ref "X13") (pin "A15") (pinfunction "A15_A15") (pintype "passive"))
      (node (ref "X14") (pin "A15") (pinfunction "A15_A15") (pintype "passive"))
      (node (ref "X15") (pin "A15") (pinfunction "A15_A15") (pintype "passive"))
      (node (ref "X16") (pin "A15") (pinfunction "A15_A15") (pintype "passive"))
      (node (ref "X17") (pin "A15") (pinfunction "A15_A15") (pintype "passive"))
      (node (ref "X18") (pin "A15") (pinfunction "A15_A15") (pintype "passive"))
      (node (ref "X19") (pin "A15") (pinfunction "A15_A15") (pintype "passive"))
      (node (ref "X2") (pin "A15") (pinfunction "A15_A15") (pintype "passive"))
      (node (ref "X20") (pin "A15") (pinfunction "A15_A15") (pintype "passive"))
      (node (ref "X3") (pin "A15") (pinfunction "A15_A15") (pintype "passive"))
      (node (ref "X4") (pin "A15") (pinfunction "A15_A15") (pintype "passive"))
      (node (ref "X5") (pin "A15") (pinfunction "A15_A15") (pintype "passive"))
      (node (ref "X6") (pin "A15") (pinfunction "A15_A15") (pintype "passive"))
      (node (ref "X7") (pin "A15") (pinfunction "A15_A15") (pintype "passive"))
      (node (ref "X8") (pin "A15") (pinfunction "A15_A15") (pintype "passive"))
      (node (ref "X9") (pin "A15") (pinfunction "A15_A15") (pintype "passive"))
    )
    (net (code "28") (name "GPIO15") (class "Default")
      (node (ref "X10") (pin "B15") (pinfunction "B15_B15") (pintype "passive"))
      (node (ref "X11") (pin "B15") (pinfunction "B15_B15") (pintype "passive"))
      (node (ref "X12") (pin "B15") (pinfunction "B15_B15") (pintype "passive"))
      (node (ref "X13") (pin "B15") (pinfunction "B15_B15") (pintype "passive"))
      (node (ref "X14") (pin "B15") (pinfunction "B15_B15") (pintype "passive"))
      (node (ref "X15") (pin "B15") (pinfunction "B15_B15") (pintype "passive"))
      (node (ref "X16") (pin "B15") (pinfunction "B15_B15") (pintype "passive"))
      (node (ref "X17") (pin "B15") (pinfunction "B15_B15") (pintype "passive"))
      (node (ref "X18") (pin "B15") (pinfunction "B15_B15") (pintype "passive"))
      (node (ref "X19") (pin "B15") (pinfunction "B15_B15") (pintype "passive"))
      (node (ref "X2") (pin "B15") (pinfunction "B15_B15") (pintype "passive"))
      (node (ref "X20") (pin "B15") (pinfunction "B15_B15") (pintype "passive"))
      (node (ref "X3") (pin "B15") (pinfunction "B15_B15") (pintype "passive"))
      (node (ref "X4") (pin "B15") (pinfunction "B15_B15") (pintype "passive"))
      (node (ref "X5") (pin "B15") (pinfunction "B15_B15") (pintype "passive"))
      (node (ref "X6") (pin "B15") (pinfunction "B15_B15") (pintype "passive"))
      (node (ref "X7") (pin "B15") (pinfunction "B15_B15") (pintype "passive"))
      (node (ref "X8") (pin "B15") (pinfunction "B15_B15") (pintype "passive"))
      (node (ref "X9") (pin "B15") (pinfunction "B15_B15") (pintype "passive"))
    )
    (net (code "29") (name "I2C_CLK") (class "Default")
      (node (ref "X1") (pin "A22") (pinfunction "A22_A22") (pintype "passive"))
      (node (ref "X10") (pin "A22") (pinfunction "A22_A22") (pintype "passive"))
      (node (ref "X11") (pin "A22") (pinfunction "A22_A22") (pintype "passive"))
      (node (ref "X12") (pin "A22") (pinfunction "A22_A22") (pintype "passive"))
      (node (ref "X13") (pin "A22") (pinfunction "A22_A22") (pintype "passive"))
      (node (ref "X14") (pin "A22") (pinfunction "A22_A22") (pintype "passive"))
      (node (ref "X15") (pin "A22") (pinfunction "A22_A22") (pintype "passive"))
      (node (ref "X16") (pin "A22") (pinfunction "A22_A22") (pintype "passive"))
      (node (ref "X17") (pin "A22") (pinfunction "A22_A22") (pintype "passive"))
      (node (ref "X18") (pin "A22") (pinfunction "A22_A22") (pintype "passive"))
      (node (ref "X19") (pin "A22") (pinfunction "A22_A22") (pintype "passive"))
      (node (ref "X2") (pin "A22") (pinfunction "A22_A22") (pintype "passive"))
      (node (ref "X20") (pin "A22") (pinfunction "A22_A22") (pintype "passive"))
      (node (ref "X3") (pin "A22") (pinfunction "A22_A22") (pintype "passive"))
      (node (ref "X4") (pin "A22") (pinfunction "A22_A22") (pintype "passive"))
      (node (ref "X5") (pin "A22") (pinfunction "A22_A22") (pintype "passive"))
      (node (ref "X6") (pin "A22") (pinfunction "A22_A22") (pintype "passive"))
      (node (ref "X7") (pin "A22") (pinfunction "A22_A22") (pintype "passive"))
      (node (ref "X8") (pin "A22") (pinfunction "A22_A22") (pintype "passive"))
      (node (ref "X9") (pin "A22") (pinfunction "A22_A22") (pintype "passive"))
    )
    (net (code "30") (name "I2C_DAT") (class "Default")
      (node (ref "X1") (pin "A23") (pinfunction "A23_A23") (pintype "passive"))
      (node (ref "X10") (pin "A23") (pinfunction "A23_A23") (pintype "passive"))
      (node (ref "X11") (pin "A23") (pinfunction "A23_A23") (pintype "passive"))
      (node (ref "X12") (pin "A23") (pinfunction "A23_A23") (pintype "passive"))
      (node (ref "X13") (pin "A23") (pinfunction "A23_A23") (pintype "passive"))
      (node (ref "X14") (pin "A23") (pinfunction "A23_A23") (pintype "passive"))
      (node (ref "X15") (pin "A23") (pinfunction "A23_A23") (pintype "passive"))
      (node (ref "X16") (pin "A23") (pinfunction "A23_A23") (pintype "passive"))
      (node (ref "X17") (pin "A23") (pinfunction "A23_A23") (pintype "passive"))
      (node (ref "X18") (pin "A23") (pinfunction "A23_A23") (pintype "passive"))
      (node (ref "X19") (pin "A23") (pinfunction "A23_A23") (pintype "passive"))
      (node (ref "X2") (pin "A23") (pinfunction "A23_A23") (pintype "passive"))
      (node (ref "X20") (pin "A23") (pinfunction "A23_A23") (pintype "passive"))
      (node (ref "X3") (pin "A23") (pinfunction "A23_A23") (pintype "passive"))
      (node (ref "X4") (pin "A23") (pinfunction "A23_A23") (pintype "passive"))
      (node (ref "X5") (pin "A23") (pinfunction "A23_A23") (pintype "passive"))
      (node (ref "X6") (pin "A23") (pinfunction "A23_A23") (pintype "passive"))
      (node (ref "X7") (pin "A23") (pinfunction "A23_A23") (pintype "passive"))
      (node (ref "X8") (pin "A23") (pinfunction "A23_A23") (pintype "passive"))
      (node (ref "X9") (pin "A23") (pinfunction "A23_A23") (pintype "passive"))
    )
    (net (code "31") (name "MAINS_INDICATOR") (class "Default")
      (node (ref "X1") (pin "A15") (pinfunction "A15_A15") (pintype "passive"))
    )
    (net (code "32") (name "MAINS_SYNC") (class "Default")
      (node (ref "X1") (pin "B15") (pinfunction "B15_B15") (pintype "passive"))
    )
    (net (code "33") (name "SPI_CLK") (class "Default")
      (node (ref "X1") (pin "A19") (pinfunction "A19_A19") (pintype "passive"))
      (node (ref "X10") (pin "A19") (pinfunction "A19_A19") (pintype "passive"))
      (node (ref "X11") (pin "A19") (pinfunction "A19_A19") (pintype "passive"))
      (node (ref "X12") (pin "A19") (pinfunction "A19_A19") (pintype "passive"))
      (node (ref "X13") (pin "A19") (pinfunction "A19_A19") (pintype "passive"))
      (node (ref "X14") (pin "A19") (pinfunction "A19_A19") (pintype "passive"))
      (node (ref "X15") (pin "A19") (pinfunction "A19_A19") (pintype "passive"))
      (node (ref "X16") (pin "A19") (pinfunction "A19_A19") (pintype "passive"))
      (node (ref "X17") (pin "A19") (pinfunction "A19_A19") (pintype "passive"))
      (node (ref "X18") (pin "A19") (pinfunction "A19_A19") (pintype "passive"))
      (node (ref "X19") (pin "A19") (pinfunction "A19_A19") (pintype "passive"))
      (node (ref "X2") (pin "A19") (pinfunction "A19_A19") (pintype "passive"))
      (node (ref "X20") (pin "A19") (pinfunction "A19_A19") (pintype "passive"))
      (node (ref "X3") (pin "A19") (pinfunction "A19_A19") (pintype "passive"))
      (node (ref "X4") (pin "A19") (pinfunction "A19_A19") (pintype "passive"))
      (node (ref "X5") (pin "A19") (pinfunction "A19_A19") (pintype "passive"))
      (node (ref "X6") (pin "A19") (pinfunction "A19_A19") (pintype "passive"))
      (node (ref "X7") (pin "A19") (pinfunction "A19_A19") (pintype "passive"))
      (node (ref "X8") (pin "A19") (pinfunction "A19_A19") (pintype "passive"))
      (node (ref "X9") (pin "A19") (pinfunction "A19_A19") (pintype "passive"))
    )
    (net (code "34") (name "SPI_MISO") (class "Default")
      (node (ref "X1") (pin "A21") (pinfunction "A21_A21") (pintype "passive"))
      (node (ref "X10") (pin "A21") (pinfunction "A21_A21") (pintype "passive"))
      (node (ref "X11") (pin "A21") (pinfunction "A21_A21") (pintype "passive"))
      (node (ref "X12") (pin "A21") (pinfunction "A21_A21") (pintype "passive"))
      (node (ref "X13") (pin "A21") (pinfunction "A21_A21") (pintype "passive"))
      (node (ref "X14") (pin "A21") (pinfunction "A21_A21") (pintype "passive"))
      (node (ref "X15") (pin "A21") (pinfunction "A21_A21") (pintype "passive"))
      (node (ref "X16") (pin "A21") (pinfunction "A21_A21") (pintype "passive"))
      (node (ref "X17") (pin "A21") (pinfunction "A21_A21") (pintype "passive"))
      (node (ref "X18") (pin "A21") (pinfunction "A21_A21") (pintype "passive"))
      (node (ref "X19") (pin "A21") (pinfunction "A21_A21") (pintype "passive"))
      (node (ref "X2") (pin "A21") (pinfunction "A21_A21") (pintype "passive"))
      (node (ref "X20") (pin "A21") (pinfunction "A21_A21") (pintype "passive"))
      (node (ref "X3") (pin "A21") (pinfunction "A21_A21") (pintype "passive"))
      (node (ref "X4") (pin "A21") (pinfunction "A21_A21") (pintype "passive"))
      (node (ref "X5") (pin "A21") (pinfunction "A21_A21") (pintype "passive"))
      (node (ref "X6") (pin "A21") (pinfunction "A21_A21") (pintype "passive"))
      (node (ref "X7") (pin "A21") (pinfunction "A21_A21") (pintype "passive"))
      (node (ref "X8") (pin "A21") (pinfunction "A21_A21") (pintype "passive"))
      (node (ref "X9") (pin "A21") (pinfunction "A21_A21") (pintype "passive"))
    )
    (net (code "35") (name "SPI_MOSI") (class "Default")
      (node (ref "X1") (pin "A20") (pinfunction "A20_A20") (pintype "passive"))
      (node (ref "X10") (pin "A20") (pinfunction "A20_A20") (pintype "passive"))
      (node (ref "X11") (pin "A20") (pinfunction "A20_A20") (pintype "passive"))
      (node (ref "X12") (pin "A20") (pinfunction "A20_A20") (pintype "passive"))
      (node (ref "X13") (pin "A20") (pinfunction "A20_A20") (pintype "passive"))
      (node (ref "X14") (pin "A20") (pinfunction "A20_A20") (pintype "passive"))
      (node (ref "X15") (pin "A20") (pinfunction "A20_A20") (pintype "passive"))
      (node (ref "X16") (pin "A20") (pinfunction "A20_A20") (pintype "passive"))
      (node (ref "X17") (pin "A20") (pinfunction "A20_A20") (pintype "passive"))
      (node (ref "X18") (pin "A20") (pinfunction "A20_A20") (pintype "passive"))
      (node (ref "X19") (pin "A20") (pinfunction "A20_A20") (pintype "passive"))
      (node (ref "X2") (pin "A20") (pinfunction "A20_A20") (pintype "passive"))
      (node (ref "X20") (pin "A20") (pinfunction "A20_A20") (pintype "passive"))
      (node (ref "X3") (pin "A20") (pinfunction "A20_A20") (pintype "passive"))
      (node (ref "X4") (pin "A20") (pinfunction "A20_A20") (pintype "passive"))
      (node (ref "X5") (pin "A20") (pinfunction "A20_A20") (pintype "passive"))
      (node (ref "X6") (pin "A20") (pinfunction "A20_A20") (pintype "passive"))
      (node (ref "X7") (pin "A20") (pinfunction "A20_A20") (pintype "passive"))
      (node (ref "X8") (pin "A20") (pinfunction "A20_A20") (pintype "passive"))
      (node (ref "X9") (pin "A20") (pinfunction "A20_A20") (pintype "passive"))
    )
    (net (code "36") (name "UC_RX") (class "Default")
      (node (ref "X1") (pin "A25") (pinfunction "A25_A25") (pintype "passive"))
      (node (ref "X10") (pin "A25") (pinfunction "A25_A25") (pintype "passive"))
      (node (ref "X11") (pin "A25") (pinfunction "A25_A25") (pintype "passive"))
      (node (ref "X12") (pin "A25") (pinfunction "A25_A25") (pintype "passive"))
      (node (ref "X13") (pin "A25") (pinfunction "A25_A25") (pintype "passive"))
      (node (ref "X14") (pin "A25") (pinfunction "A25_A25") (pintype "passive"))
      (node (ref "X15") (pin "A25") (pinfunction "A25_A25") (pintype "passive"))
      (node (ref "X16") (pin "A25") (pinfunction "A25_A25") (pintype "passive"))
      (node (ref "X17") (pin "A25") (pinfunction "A25_A25") (pintype "passive"))
      (node (ref "X18") (pin "A25") (pinfunction "A25_A25") (pintype "passive"))
      (node (ref "X19") (pin "A25") (pinfunction "A25_A25") (pintype "passive"))
      (node (ref "X2") (pin "A25") (pinfunction "A25_A25") (pintype "passive"))
      (node (ref "X20") (pin "A25") (pinfunction "A25_A25") (pintype "passive"))
      (node (ref "X3") (pin "A25") (pinfunction "A25_A25") (pintype "passive"))
      (node (ref "X4") (pin "A25") (pinfunction "A25_A25") (pintype "passive"))
      (node (ref "X5") (pin "A25") (pinfunction "A25_A25") (pintype "passive"))
      (node (ref "X6") (pin "A25") (pinfunction "A25_A25") (pintype "passive"))
      (node (ref "X7") (pin "A25") (pinfunction "A25_A25") (pintype "passive"))
      (node (ref "X8") (pin "A25") (pinfunction "A25_A25") (pintype "passive"))
      (node (ref "X9") (pin "A25") (pinfunction "A25_A25") (pintype "passive"))
    )
    (net (code "37") (name "UC_TX") (class "Default")
      (node (ref "X1") (pin "A24") (pinfunction "A24_A24") (pintype "passive"))
      (node (ref "X10") (pin "A24") (pinfunction "A24_A24") (pintype "passive"))
      (node (ref "X11") (pin "A24") (pinfunction "A24_A24") (pintype "passive"))
      (node (ref "X12") (pin "A24") (pinfunction "A24_A24") (pintype "passive"))
      (node (ref "X13") (pin "A24") (pinfunction "A24_A24") (pintype "passive"))
      (node (ref "X14") (pin "A24") (pinfunction "A24_A24") (pintype "passive"))
      (node (ref "X15") (pin "A24") (pinfunction "A24_A24") (pintype "passive"))
      (node (ref "X16") (pin "A24") (pinfunction "A24_A24") (pintype "passive"))
      (node (ref "X17") (pin "A24") (pinfunction "A24_A24") (pintype "passive"))
      (node (ref "X18") (pin "A24") (pinfunction "A24_A24") (pintype "passive"))
      (node (ref "X19") (pin "A24") (pinfunction "A24_A24") (pintype "passive"))
      (node (ref "X2") (pin "A24") (pinfunction "A24_A24") (pintype "passive"))
      (node (ref "X20") (pin "A24") (pinfunction "A24_A24") (pintype "passive"))
      (node (ref "X3") (pin "A24") (pinfunction "A24_A24") (pintype "passive"))
      (node (ref "X4") (pin "A24") (pinfunction "A24_A24") (pintype "passive"))
      (node (ref "X5") (pin "A24") (pinfunction "A24_A24") (pintype "passive"))
      (node (ref "X6") (pin "A24") (pinfunction "A24_A24") (pintype "passive"))
      (node (ref "X7") (pin "A24") (pinfunction "A24_A24") (pintype "passive"))
      (node (ref "X8") (pin "A24") (pinfunction "A24_A24") (pintype "passive"))
      (node (ref "X9") (pin "A24") (pinfunction "A24_A24") (pintype "passive"))
    )
  )
)
